# LHC_Clock.net
KiCad netlist of a schematic drawn in Altium Designer
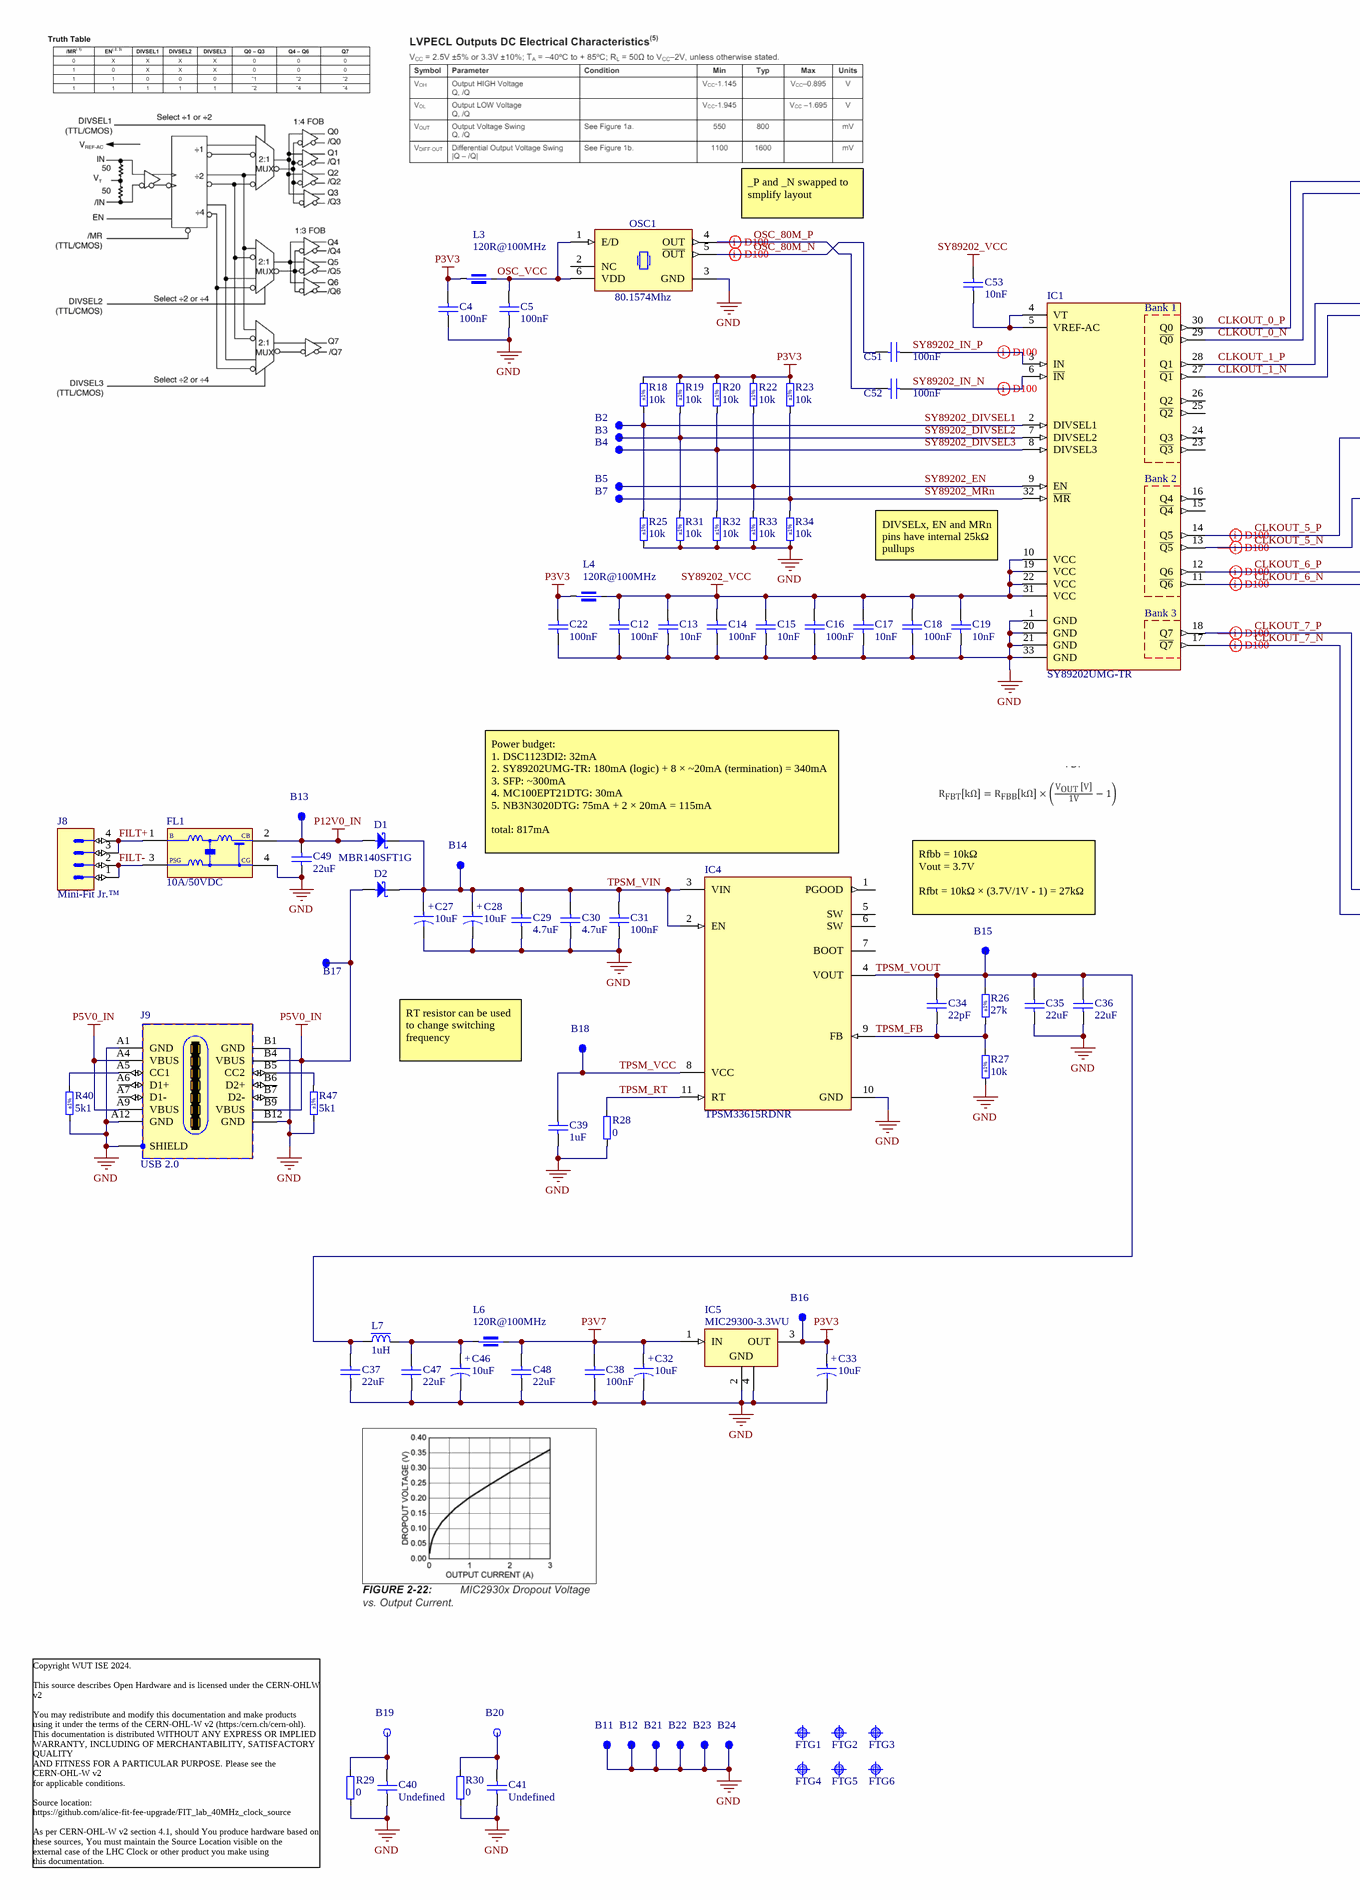
[diagram p0: LHC_Clock.SchDoc, left]
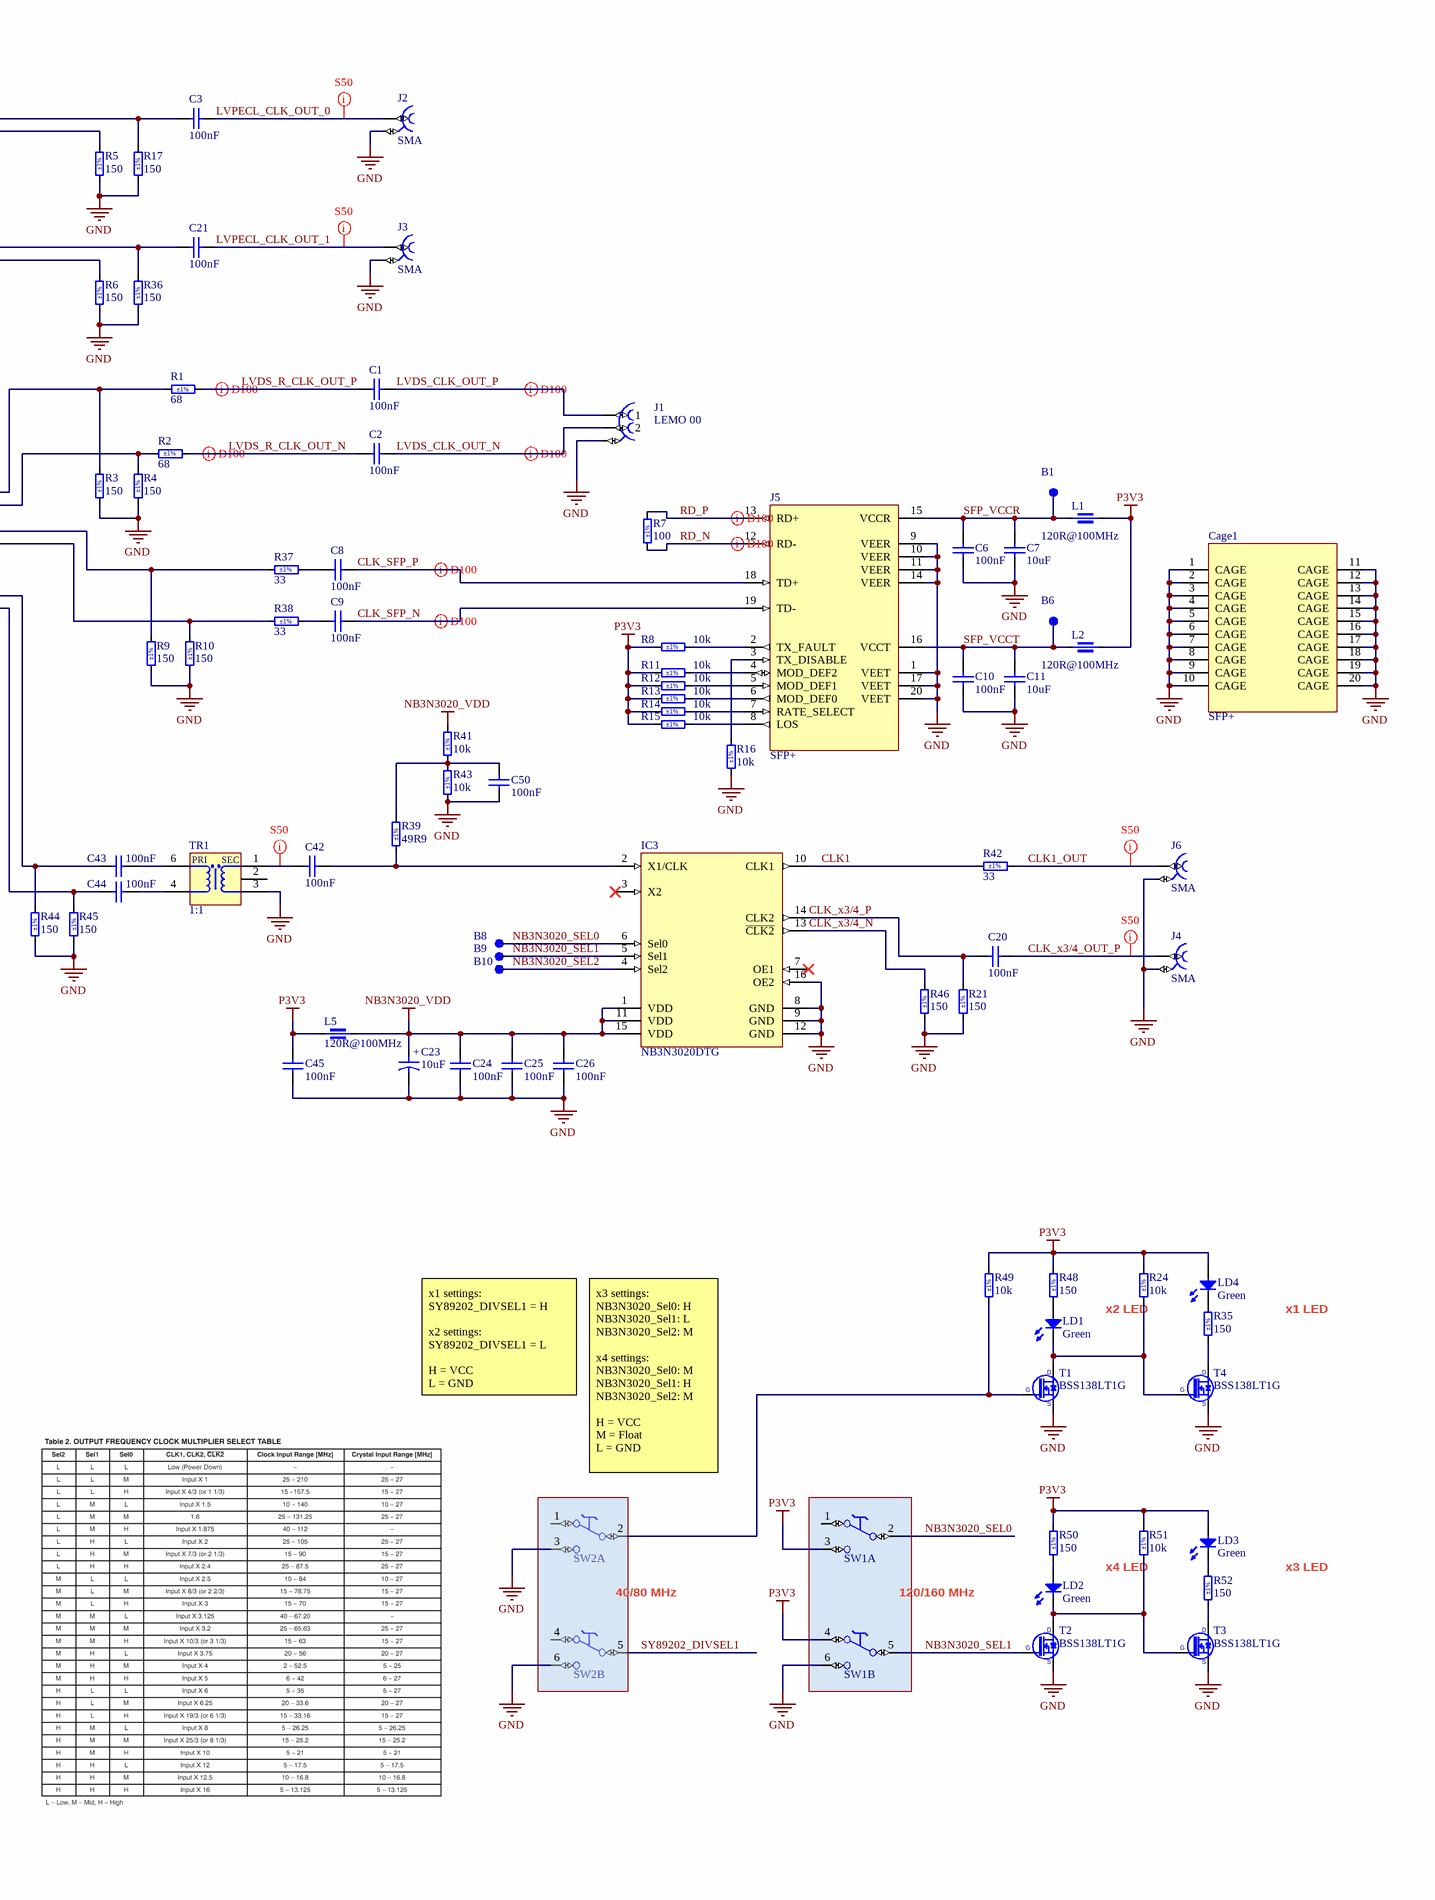
[diagram p1: LHC_Clock.SchDoc, right]

(export (version "E")
  (design (tool "Eeschema 10.0.6"))
  (components
    (comp (ref "B1")
      (value "SMD Pad")
      (footprint "C100")
      (description "Pad")
      (fields (field (name "PART NUMBER") "SMD_PAD_D1MM") (field (name "AUTHOR") "CERN DEM JLC"))
      (libsource (lib "Eletro-mechanical") (part "Single SMD Pad (Round)"))
    )
    (comp (ref "B2")
      (value "SMD Pad")
      (footprint "C100")
      (description "Pad")
      (fields (field (name "PART NUMBER") "SMD_PAD_D1MM") (field (name "AUTHOR") "CERN DEM JLC"))
      (libsource (lib "Eletro-mechanical") (part "Single SMD Pad (Round)"))
    )
    (comp (ref "B3")
      (value "SMD Pad")
      (footprint "C100")
      (description "Pad")
      (fields (field (name "PART NUMBER") "SMD_PAD_D1MM") (field (name "AUTHOR") "CERN DEM JLC"))
      (libsource (lib "Eletro-mechanical") (part "Single SMD Pad (Round)"))
    )
    (comp (ref "B4")
      (value "SMD Pad")
      (footprint "C100")
      (description "Pad")
      (fields (field (name "PART NUMBER") "SMD_PAD_D1MM") (field (name "AUTHOR") "CERN DEM JLC"))
      (libsource (lib "Eletro-mechanical") (part "Single SMD Pad (Round)"))
    )
    (comp (ref "B5")
      (value "SMD Pad")
      (footprint "C100")
      (description "Pad")
      (fields (field (name "PART NUMBER") "SMD_PAD_D1MM") (field (name "AUTHOR") "CERN DEM JLC"))
      (libsource (lib "Eletro-mechanical") (part "Single SMD Pad (Round)"))
    )
    (comp (ref "B6")
      (value "SMD Pad")
      (footprint "C100")
      (description "Pad")
      (fields (field (name "PART NUMBER") "SMD_PAD_D1MM") (field (name "AUTHOR") "CERN DEM JLC"))
      (libsource (lib "Eletro-mechanical") (part "Single SMD Pad (Round)"))
    )
    (comp (ref "B7")
      (value "SMD Pad")
      (footprint "C100")
      (description "Pad")
      (fields (field (name "PART NUMBER") "SMD_PAD_D1MM") (field (name "AUTHOR") "CERN DEM JLC"))
      (libsource (lib "Eletro-mechanical") (part "Single SMD Pad (Round)"))
    )
    (comp (ref "B8")
      (value "SMD Pad")
      (footprint "C100")
      (description "Pad")
      (fields (field (name "PART NUMBER") "SMD_PAD_D1MM") (field (name "AUTHOR") "CERN DEM JLC"))
      (libsource (lib "Eletro-mechanical") (part "Single SMD Pad (Round)"))
    )
    (comp (ref "B9")
      (value "SMD Pad")
      (footprint "C100")
      (description "Pad")
      (fields (field (name "PART NUMBER") "SMD_PAD_D1MM") (field (name "AUTHOR") "CERN DEM JLC"))
      (libsource (lib "Eletro-mechanical") (part "Single SMD Pad (Round)"))
    )
    (comp (ref "B10")
      (value "SMD Pad")
      (footprint "C100")
      (description "Pad")
      (fields (field (name "PART NUMBER") "SMD_PAD_D1MM") (field (name "AUTHOR") "CERN DEM JLC"))
      (libsource (lib "Eletro-mechanical") (part "Single SMD Pad (Round)"))
    )
    (comp (ref "B11")
      (value "SMD Pad")
      (footprint "C100")
      (description "Pad")
      (fields (field (name "PART NUMBER") "SMD_PAD_D1MM") (field (name "AUTHOR") "CERN DEM JLC"))
      (libsource (lib "Eletro-mechanical") (part "Single SMD Pad (Round)"))
    )
    (comp (ref "B12")
      (value "SMD Pad")
      (footprint "C100")
      (description "Pad")
      (fields (field (name "PART NUMBER") "SMD_PAD_D1MM") (field (name "AUTHOR") "CERN DEM JLC"))
      (libsource (lib "Eletro-mechanical") (part "Single SMD Pad (Round)"))
    )
    (comp (ref "B13")
      (value "SMD Pad")
      (footprint "C100")
      (description "Pad")
      (fields (field (name "PART NUMBER") "SMD_PAD_D1MM") (field (name "AUTHOR") "CERN DEM JLC"))
      (libsource (lib "Eletro-mechanical") (part "Single SMD Pad (Round)"))
    )
    (comp (ref "B14")
      (value "SMD Pad")
      (footprint "C100")
      (description "Pad")
      (fields (field (name "PART NUMBER") "SMD_PAD_D1MM") (field (name "AUTHOR") "CERN DEM JLC"))
      (libsource (lib "Eletro-mechanical") (part "Single SMD Pad (Round)"))
    )
    (comp (ref "B15")
      (value "SMD Pad")
      (footprint "C100")
      (description "Pad")
      (fields (field (name "PART NUMBER") "SMD_PAD_D1MM") (field (name "AUTHOR") "CERN DEM JLC"))
      (libsource (lib "Eletro-mechanical") (part "Single SMD Pad (Round)"))
    )
    (comp (ref "B16")
      (value "SMD Pad")
      (footprint "C100")
      (description "Pad")
      (fields (field (name "PART NUMBER") "SMD_PAD_D1MM") (field (name "AUTHOR") "CERN DEM JLC"))
      (libsource (lib "Eletro-mechanical") (part "Single SMD Pad (Round)"))
    )
    (comp (ref "B17")
      (value "SMD Pad")
      (footprint "C100")
      (description "Pad")
      (fields (field (name "PART NUMBER") "SMD_PAD_D1MM") (field (name "AUTHOR") "CERN DEM JLC"))
      (libsource (lib "Eletro-mechanical") (part "Single SMD Pad (Round)"))
    )
    (comp (ref "B18")
      (value "SMD Pad")
      (footprint "C100")
      (description "Pad")
      (fields (field (name "PART NUMBER") "SMD_PAD_D1MM") (field (name "AUTHOR") "CERN DEM JLC"))
      (libsource (lib "Eletro-mechanical") (part "Single SMD Pad (Round)"))
    )
    (comp (ref "B19")
      (value "Plated Hole")
      (footprint "MTG270_500")
      (description "Single Terminal Socket")
      (fields (field (name "PART NUMBER") "PLATED_HOLE2.7_PAD5.0") (field (name "AUTHOR") "CERN DEM JMW"))
      (libsource (lib "Eletro-mechanical") (part "Single Terminal Socket"))
    )
    (comp (ref "B20")
      (value "Plated Hole")
      (footprint "MTG270_500")
      (description "Single Terminal Socket")
      (fields (field (name "PART NUMBER") "PLATED_HOLE2.7_PAD5.0") (field (name "AUTHOR") "CERN DEM JMW"))
      (libsource (lib "Eletro-mechanical") (part "Single Terminal Socket"))
    )
    (comp (ref "B21")
      (value "SMD Pad")
      (footprint "C100")
      (description "Pad")
      (fields (field (name "PART NUMBER") "SMD_PAD_D1MM") (field (name "AUTHOR") "CERN DEM JLC"))
      (libsource (lib "Eletro-mechanical") (part "Single SMD Pad (Round)"))
    )
    (comp (ref "B22")
      (value "SMD Pad")
      (footprint "C100")
      (description "Pad")
      (fields (field (name "PART NUMBER") "SMD_PAD_D1MM") (field (name "AUTHOR") "CERN DEM JLC"))
      (libsource (lib "Eletro-mechanical") (part "Single SMD Pad (Round)"))
    )
    (comp (ref "B23")
      (value "SMD Pad")
      (footprint "C100")
      (description "Pad")
      (fields (field (name "PART NUMBER") "SMD_PAD_D1MM") (field (name "AUTHOR") "CERN DEM JLC"))
      (libsource (lib "Eletro-mechanical") (part "Single SMD Pad (Round)"))
    )
    (comp (ref "B24")
      (value "SMD Pad")
      (footprint "C100")
      (description "Pad")
      (fields (field (name "PART NUMBER") "SMD_PAD_D1MM") (field (name "AUTHOR") "CERN DEM JLC"))
      (libsource (lib "Eletro-mechanical") (part "Single SMD Pad (Round)"))
    )
    (comp (ref "C1")
      (value "100nF")
      (footprint "CAPC1005X55N")
      (description "Non-polarised capacitor")
      (fields
        (field (name "PART NUMBER") "CC0402_100NF_50V_10%_X7R")
        (field (name "VOLTAGE") "50V")
        (field (name "AUTHOR") "CERN DEM MR")
      )
      (libsource (lib "Capacitors") (part "Capacitor - non polarized"))
    )
    (comp (ref "C2")
      (value "100nF")
      (footprint "CAPC1005X55N")
      (description "Non-polarised capacitor")
      (fields
        (field (name "PART NUMBER") "CC0402_100NF_50V_10%_X7R")
        (field (name "VOLTAGE") "50V")
        (field (name "AUTHOR") "CERN DEM MR")
      )
      (libsource (lib "Capacitors") (part "Capacitor - non polarized"))
    )
    (comp (ref "C3")
      (value "100nF")
      (footprint "CAPC1005X55N")
      (description "Non-polarised capacitor")
      (fields
        (field (name "PART NUMBER") "CC0402_100NF_50V_10%_X7R")
        (field (name "VOLTAGE") "50V")
        (field (name "AUTHOR") "CERN DEM MR")
      )
      (libsource (lib "Capacitors") (part "Capacitor - non polarized"))
    )
    (comp (ref "C4")
      (value "100nF")
      (footprint "CAPC1005X55N")
      (description "Non-polarised capacitor")
      (fields
        (field (name "PART NUMBER") "CC0402_100NF_50V_10%_X7R")
        (field (name "VOLTAGE") "50V")
        (field (name "AUTHOR") "CERN DEM MR")
      )
      (libsource (lib "Capacitors") (part "Capacitor - non polarized"))
    )
    (comp (ref "C5")
      (value "100nF")
      (footprint "CAPC1005X55N")
      (description "Non-polarised capacitor")
      (fields
        (field (name "PART NUMBER") "CC0402_100NF_50V_10%_X7R")
        (field (name "VOLTAGE") "50V")
        (field (name "AUTHOR") "CERN DEM MR")
      )
      (libsource (lib "Capacitors") (part "Capacitor - non polarized"))
    )
    (comp (ref "C6")
      (value "100nF")
      (footprint "CAPC1005X55N")
      (description "Non-polarised capacitor")
      (fields
        (field (name "PART NUMBER") "CC0402_100NF_50V_10%_X7R")
        (field (name "VOLTAGE") "50V")
        (field (name "AUTHOR") "CERN DEM MR")
      )
      (libsource (lib "Capacitors") (part "Capacitor - non polarized"))
    )
    (comp (ref "C7")
      (value "10uF")
      (footprint "CAPC1608X80N")
      (description "Non-polarised capacitor")
      (fields
        (field (name "PART NUMBER") "CC0603_10UF_16V_20%_X5R")
        (field (name "VOLTAGE") "16V")
        (field (name "AUTHOR") "CERN DEM MR")
      )
      (libsource (lib "Capacitors") (part "Capacitor - non polarized"))
    )
    (comp (ref "C8")
      (value "100nF")
      (footprint "CAPC1005X55N")
      (description "Non-polarised capacitor")
      (fields
        (field (name "PART NUMBER") "CC0402_100NF_50V_10%_X7R")
        (field (name "VOLTAGE") "50V")
        (field (name "AUTHOR") "CERN DEM MR")
      )
      (libsource (lib "Capacitors") (part "Capacitor - non polarized"))
    )
    (comp (ref "C9")
      (value "100nF")
      (footprint "CAPC1005X55N")
      (description "Non-polarised capacitor")
      (fields
        (field (name "PART NUMBER") "CC0402_100NF_50V_10%_X7R")
        (field (name "VOLTAGE") "50V")
        (field (name "AUTHOR") "CERN DEM MR")
      )
      (libsource (lib "Capacitors") (part "Capacitor - non polarized"))
    )
    (comp (ref "C10")
      (value "100nF")
      (footprint "CAPC1005X55N")
      (description "Non-polarised capacitor")
      (fields
        (field (name "PART NUMBER") "CC0402_100NF_50V_10%_X7R")
        (field (name "VOLTAGE") "50V")
        (field (name "AUTHOR") "CERN DEM MR")
      )
      (libsource (lib "Capacitors") (part "Capacitor - non polarized"))
    )
    (comp (ref "C11")
      (value "10uF")
      (footprint "CAPC1608X80N")
      (description "Non-polarised capacitor")
      (fields
        (field (name "PART NUMBER") "CC0603_10UF_16V_20%_X5R")
        (field (name "VOLTAGE") "16V")
        (field (name "AUTHOR") "CERN DEM MR")
      )
      (libsource (lib "Capacitors") (part "Capacitor - non polarized"))
    )
    (comp (ref "C12")
      (value "100nF")
      (footprint "CAPC1005X55N")
      (description "Non-polarised capacitor")
      (fields
        (field (name "PART NUMBER") "CC0402_100NF_50V_10%_X7R")
        (field (name "VOLTAGE") "50V")
        (field (name "AUTHOR") "CERN DEM MR")
      )
      (libsource (lib "Capacitors") (part "Capacitor - non polarized"))
    )
    (comp (ref "C13")
      (value "10nF")
      (footprint "CAPC1005X55N")
      (description "Non-polarised capacitor")
      (fields
        (field (name "PART NUMBER") "CC0402_10NF_50V_10%_X7R")
        (field (name "VOLTAGE") "50V")
        (field (name "AUTHOR") "CERN DEM MR")
      )
      (libsource (lib "Capacitors") (part "Capacitor - non polarized"))
    )
    (comp (ref "C14")
      (value "100nF")
      (footprint "CAPC1005X55N")
      (description "Non-polarised capacitor")
      (fields
        (field (name "PART NUMBER") "CC0402_100NF_50V_10%_X7R")
        (field (name "VOLTAGE") "50V")
        (field (name "AUTHOR") "CERN DEM MR")
      )
      (libsource (lib "Capacitors") (part "Capacitor - non polarized"))
    )
    (comp (ref "C15")
      (value "10nF")
      (footprint "CAPC1005X55N")
      (description "Non-polarised capacitor")
      (fields
        (field (name "PART NUMBER") "CC0402_10NF_50V_10%_X7R")
        (field (name "VOLTAGE") "50V")
        (field (name "AUTHOR") "CERN DEM MR")
      )
      (libsource (lib "Capacitors") (part "Capacitor - non polarized"))
    )
    (comp (ref "C16")
      (value "100nF")
      (footprint "CAPC1005X55N")
      (description "Non-polarised capacitor")
      (fields
        (field (name "PART NUMBER") "CC0402_100NF_50V_10%_X7R")
        (field (name "VOLTAGE") "50V")
        (field (name "AUTHOR") "CERN DEM MR")
      )
      (libsource (lib "Capacitors") (part "Capacitor - non polarized"))
    )
    (comp (ref "C17")
      (value "10nF")
      (footprint "CAPC1005X55N")
      (description "Non-polarised capacitor")
      (fields
        (field (name "PART NUMBER") "CC0402_10NF_50V_10%_X7R")
        (field (name "VOLTAGE") "50V")
        (field (name "AUTHOR") "CERN DEM MR")
      )
      (libsource (lib "Capacitors") (part "Capacitor - non polarized"))
    )
    (comp (ref "C18")
      (value "100nF")
      (footprint "CAPC1005X55N")
      (description "Non-polarised capacitor")
      (fields
        (field (name "PART NUMBER") "CC0402_100NF_50V_10%_X7R")
        (field (name "VOLTAGE") "50V")
        (field (name "AUTHOR") "CERN DEM MR")
      )
      (libsource (lib "Capacitors") (part "Capacitor - non polarized"))
    )
    (comp (ref "C19")
      (value "10nF")
      (footprint "CAPC1005X55N")
      (description "Non-polarised capacitor")
      (fields
        (field (name "PART NUMBER") "CC0402_10NF_50V_10%_X7R")
        (field (name "VOLTAGE") "50V")
        (field (name "AUTHOR") "CERN DEM MR")
      )
      (libsource (lib "Capacitors") (part "Capacitor - non polarized"))
    )
    (comp (ref "C20")
      (value "100nF")
      (footprint "CAPC1005X55N")
      (description "Non-polarised capacitor")
      (fields
        (field (name "PART NUMBER") "CC0402_100NF_50V_10%_X7R")
        (field (name "VOLTAGE") "50V")
        (field (name "AUTHOR") "CERN DEM MR")
      )
      (libsource (lib "Capacitors") (part "Capacitor - non polarized"))
    )
    (comp (ref "C21")
      (value "100nF")
      (footprint "CAPC1005X55N")
      (description "Non-polarised capacitor")
      (fields
        (field (name "PART NUMBER") "CC0402_100NF_50V_10%_X7R")
        (field (name "VOLTAGE") "50V")
        (field (name "AUTHOR") "CERN DEM MR")
      )
      (libsource (lib "Capacitors") (part "Capacitor - non polarized"))
    )
    (comp (ref "C22")
      (value "100nF")
      (footprint "CAPC1005X55N")
      (description "Non-polarised capacitor")
      (fields
        (field (name "PART NUMBER") "CC0402_100NF_50V_10%_X7R")
        (field (name "VOLTAGE") "50V")
        (field (name "AUTHOR") "CERN DEM MR")
      )
      (libsource (lib "Capacitors") (part "Capacitor - non polarized"))
    )
    (comp (ref "C23")
      (value "10uF")
      (footprint "CAPMP3216X180N")
      (description "Polarised capacitor")
      (fields
        (field (name "PART NUMBER") "CTE3216-18_10UF_16V_20%_AVX_TCJ")
        (field (name "VOLTAGE") "16V")
        (field (name "AUTHOR") "CERN DEM JLC")
      )
      (libsource (lib "Capacitors") (part "Capacitor - polarized"))
    )
    (comp (ref "C24")
      (value "100nF")
      (footprint "CAPC1005X55N")
      (description "Non-polarised capacitor")
      (fields
        (field (name "PART NUMBER") "CC0402_100NF_50V_10%_X7R")
        (field (name "VOLTAGE") "50V")
        (field (name "AUTHOR") "CERN DEM MR")
      )
      (libsource (lib "Capacitors") (part "Capacitor - non polarized"))
    )
    (comp (ref "C25")
      (value "100nF")
      (footprint "CAPC1005X55N")
      (description "Non-polarised capacitor")
      (fields
        (field (name "PART NUMBER") "CC0402_100NF_50V_10%_X7R")
        (field (name "VOLTAGE") "50V")
        (field (name "AUTHOR") "CERN DEM MR")
      )
      (libsource (lib "Capacitors") (part "Capacitor - non polarized"))
    )
    (comp (ref "C26")
      (value "100nF")
      (footprint "CAPC1005X55N")
      (description "Non-polarised capacitor")
      (fields
        (field (name "PART NUMBER") "CC0402_100NF_50V_10%_X7R")
        (field (name "VOLTAGE") "50V")
        (field (name "AUTHOR") "CERN DEM MR")
      )
      (libsource (lib "Capacitors") (part "Capacitor - non polarized"))
    )
    (comp (ref "C27")
      (value "10uF")
      (footprint "CAPMP3216X180N")
      (description "Polarised capacitor")
      (fields
        (field (name "PART NUMBER") "CTE3216-18_10UF_16V_20%_AVX_TCJ")
        (field (name "VOLTAGE") "16V")
        (field (name "AUTHOR") "CERN DEM JLC")
      )
      (libsource (lib "Capacitors") (part "Capacitor - polarized"))
    )
    (comp (ref "C28")
      (value "10uF")
      (footprint "CAPMP3216X180N")
      (description "Polarised capacitor")
      (fields
        (field (name "PART NUMBER") "CTE3216-18_10UF_16V_20%_AVX_TCJ")
        (field (name "VOLTAGE") "16V")
        (field (name "AUTHOR") "CERN DEM JLC")
      )
      (libsource (lib "Capacitors") (part "Capacitor - polarized"))
    )
    (comp (ref "C29")
      (value "4.7uF")
      (footprint "CAPC1608X90N")
      (description "Non-polarised capacitor")
      (fields
        (field (name "PART NUMBER") "CC0603_4.7UF_25V_10%_X5R")
        (field (name "VOLTAGE") "25V")
        (field (name "AUTHOR") "CERN DEM JLC")
      )
      (libsource (lib "Capacitors") (part "Capacitor - non polarized"))
    )
    (comp (ref "C30")
      (value "4.7uF")
      (footprint "CAPC1608X90N")
      (description "Non-polarised capacitor")
      (fields
        (field (name "PART NUMBER") "CC0603_4.7UF_25V_10%_X5R")
        (field (name "VOLTAGE") "25V")
        (field (name "AUTHOR") "CERN DEM JLC")
      )
      (libsource (lib "Capacitors") (part "Capacitor - non polarized"))
    )
    (comp (ref "C31")
      (value "100nF")
      (footprint "CAPC1005X55N")
      (description "Non-polarised capacitor")
      (fields
        (field (name "PART NUMBER") "CC0402_100NF_50V_10%_X7R")
        (field (name "VOLTAGE") "50V")
        (field (name "AUTHOR") "CERN DEM MR")
      )
      (libsource (lib "Capacitors") (part "Capacitor - non polarized"))
    )
    (comp (ref "C32")
      (value "10uF")
      (footprint "CAPMP3216X180N")
      (description "Polarised capacitor")
      (fields
        (field (name "PART NUMBER") "CTE3216-18_10UF_16V_20%_AVX_TCJ")
        (field (name "VOLTAGE") "16V")
        (field (name "AUTHOR") "CERN DEM JLC")
      )
      (libsource (lib "Capacitors") (part "Capacitor - polarized"))
    )
    (comp (ref "C33")
      (value "10uF")
      (footprint "CAPMP3216X180N")
      (description "Polarised capacitor")
      (fields
        (field (name "PART NUMBER") "CTE3216-18_10UF_16V_20%_AVX_TCJ")
        (field (name "VOLTAGE") "16V")
        (field (name "AUTHOR") "CERN DEM JLC")
      )
      (libsource (lib "Capacitors") (part "Capacitor - polarized"))
    )
    (comp (ref "C34")
      (value "22pF")
      (footprint "CAPC1005X55N")
      (description "Non-polarised capacitor")
      (fields
        (field (name "PART NUMBER") "CC0402_22PF_50V_5%_C0G")
        (field (name "VOLTAGE") "50V")
        (field (name "AUTHOR") "CERN DEM JLC")
      )
      (libsource (lib "Capacitors") (part "Capacitor - non polarized"))
    )
    (comp (ref "C35")
      (value "22uF")
      (footprint "CAPC2012X135N")
      (description "Non-polarised capacitor")
      (fields
        (field (name "PART NUMBER") "CC0805_22UF_16V_10%_X5R")
        (field (name "VOLTAGE") "16V")
        (field (name "AUTHOR") "CERN DEM JLC")
      )
      (libsource (lib "Capacitors") (part "Capacitor - non polarized"))
    )
    (comp (ref "C36")
      (value "22uF")
      (footprint "CAPC2012X135N")
      (description "Non-polarised capacitor")
      (fields
        (field (name "PART NUMBER") "CC0805_22UF_16V_10%_X5R")
        (field (name "VOLTAGE") "16V")
        (field (name "AUTHOR") "CERN DEM JLC")
      )
      (libsource (lib "Capacitors") (part "Capacitor - non polarized"))
    )
    (comp (ref "C37")
      (value "22uF")
      (footprint "CAPC2012X135N")
      (description "Non-polarised capacitor")
      (fields
        (field (name "PART NUMBER") "CC0805_22UF_16V_10%_X5R")
        (field (name "VOLTAGE") "16V")
        (field (name "AUTHOR") "CERN DEM JLC")
      )
      (libsource (lib "Capacitors") (part "Capacitor - non polarized"))
    )
    (comp (ref "C38")
      (value "100nF")
      (footprint "CAPC1005X55N")
      (description "Non-polarised capacitor")
      (fields
        (field (name "PART NUMBER") "CC0402_100NF_50V_10%_X7R")
        (field (name "VOLTAGE") "50V")
        (field (name "AUTHOR") "CERN DEM MR")
      )
      (libsource (lib "Capacitors") (part "Capacitor - non polarized"))
    )
    (comp (ref "C39")
      (value "1uF")
      (footprint "CAPC1608X87N")
      (description "Non-polarised capacitor")
      (fields
        (field (name "PART NUMBER") "CC0603_1UF_16V_10%_X7R")
        (field (name "VOLTAGE") "16V")
        (field (name "AUTHOR") "CERN DEM JLC")
      )
      (libsource (lib "Capacitors") (part "Capacitor - non polarized"))
    )
    (comp (ref "C40")
      (value "Undefined")
      (footprint "CAPC2012X135N")
      (description "Non-polarised capacitor")
      (fields (field (name "PART NUMBER") "CC0805_NO-VALUE") (field (name "AUTHOR") "CERN DEM JLC"))
      (libsource (lib "Capacitors") (part "Capacitor - non polarized"))
    )
    (comp (ref "C41")
      (value "Undefined")
      (footprint "CAPC2012X135N")
      (description "Non-polarised capacitor")
      (fields (field (name "PART NUMBER") "CC0805_NO-VALUE") (field (name "AUTHOR") "CERN DEM JLC"))
      (libsource (lib "Capacitors") (part "Capacitor - non polarized"))
    )
    (comp (ref "C42")
      (value "100nF")
      (footprint "CAPC1005X55N")
      (description "Non-polarised capacitor")
      (fields
        (field (name "PART NUMBER") "CC0402_100NF_50V_10%_X7R")
        (field (name "VOLTAGE") "50V")
        (field (name "AUTHOR") "CERN DEM MR")
      )
      (libsource (lib "Capacitors") (part "Capacitor - non polarized"))
    )
    (comp (ref "C43")
      (value "100nF")
      (footprint "CAPC1005X55N")
      (description "Non-polarised capacitor")
      (fields
        (field (name "PART NUMBER") "CC0402_100NF_50V_10%_X7R")
        (field (name "VOLTAGE") "50V")
        (field (name "AUTHOR") "CERN DEM MR")
      )
      (libsource (lib "Capacitors") (part "Capacitor - non polarized"))
    )
    (comp (ref "C44")
      (value "100nF")
      (footprint "CAPC1005X55N")
      (description "Non-polarised capacitor")
      (fields
        (field (name "PART NUMBER") "CC0402_100NF_50V_10%_X7R")
        (field (name "VOLTAGE") "50V")
        (field (name "AUTHOR") "CERN DEM MR")
      )
      (libsource (lib "Capacitors") (part "Capacitor - non polarized"))
    )
    (comp (ref "C45")
      (value "100nF")
      (footprint "CAPC1005X55N")
      (description "Non-polarised capacitor")
      (fields
        (field (name "PART NUMBER") "CC0402_100NF_50V_10%_X7R")
        (field (name "VOLTAGE") "50V")
        (field (name "AUTHOR") "CERN DEM MR")
      )
      (libsource (lib "Capacitors") (part "Capacitor - non polarized"))
    )
    (comp (ref "C46")
      (value "10uF")
      (footprint "CAPMP3216X180N")
      (description "Polarised capacitor")
      (fields
        (field (name "PART NUMBER") "CTE3216-18_10UF_16V_20%_AVX_TCJ")
        (field (name "VOLTAGE") "16V")
        (field (name "AUTHOR") "CERN DEM JLC")
      )
      (libsource (lib "Capacitors") (part "Capacitor - polarized"))
    )
    (comp (ref "C47")
      (value "22uF")
      (footprint "CAPC2012X135N")
      (description "Non-polarised capacitor")
      (fields
        (field (name "PART NUMBER") "CC0805_22UF_16V_10%_X5R")
        (field (name "VOLTAGE") "16V")
        (field (name "AUTHOR") "CERN DEM JLC")
      )
      (libsource (lib "Capacitors") (part "Capacitor - non polarized"))
    )
    (comp (ref "C48")
      (value "22uF")
      (footprint "CAPC2012X135N")
      (description "Non-polarised capacitor")
      (fields
        (field (name "PART NUMBER") "CC0805_22UF_16V_10%_X5R")
        (field (name "VOLTAGE") "16V")
        (field (name "AUTHOR") "CERN DEM JLC")
      )
      (libsource (lib "Capacitors") (part "Capacitor - non polarized"))
    )
    (comp (ref "C49")
      (value "22uF")
      (footprint "CAPC2012X135N")
      (description "Non-polarised capacitor")
      (fields
        (field (name "PART NUMBER") "CC0805_22UF_16V_10%_X5R")
        (field (name "VOLTAGE") "16V")
        (field (name "AUTHOR") "CERN DEM JLC")
      )
      (libsource (lib "Capacitors") (part "Capacitor - non polarized"))
    )
    (comp (ref "C50")
      (value "100nF")
      (footprint "CAPC1005X55N")
      (description "Non-polarised capacitor")
      (fields
        (field (name "PART NUMBER") "CC0402_100NF_50V_10%_X7R")
        (field (name "VOLTAGE") "50V")
        (field (name "AUTHOR") "CERN DEM MR")
      )
      (libsource (lib "Capacitors") (part "Capacitor - non polarized"))
    )
    (comp (ref "C51")
      (value "100nF")
      (footprint "CAPC1005X55N")
      (description "Non-polarised capacitor")
      (fields
        (field (name "PART NUMBER") "CC0402_100NF_50V_10%_X7R")
        (field (name "VOLTAGE") "50V")
        (field (name "AUTHOR") "CERN DEM MR")
      )
      (libsource (lib "Capacitors") (part "Capacitor - non polarized"))
    )
    (comp (ref "C52")
      (value "100nF")
      (footprint "CAPC1005X55N")
      (description "Non-polarised capacitor")
      (fields
        (field (name "PART NUMBER") "CC0402_100NF_50V_10%_X7R")
        (field (name "VOLTAGE") "50V")
        (field (name "AUTHOR") "CERN DEM MR")
      )
      (libsource (lib "Capacitors") (part "Capacitor - non polarized"))
    )
    (comp (ref "C53")
      (value "10nF")
      (footprint "CAPC1005X55N")
      (description "Non-polarised capacitor")
      (fields
        (field (name "PART NUMBER") "CC0402_10NF_50V_10%_X7R")
        (field (name "VOLTAGE") "50V")
        (field (name "AUTHOR") "CERN DEM MR")
      )
      (libsource (lib "Capacitors") (part "Capacitor - non polarized"))
    )
    (comp (ref "Cage1")
      (value "SFP+")
      (footprint "MOLEX_74737-0009")
      (description "SFP+ 1x1 Cage (20Pins)")
      (fields
        (field (name "PART NUMBER") "MOLEX_74737-0009")
        (field (name "MANUFACTURER") "MOLEX")
        (field (name "AUTHOR") "CERN DEM MR")
      )
      (libsource (lib "Connectors") (part "SFP+ 1x1 Cage (20Pins)"))
    )
    (comp (ref "D1")
      (value "MBR140SFT1G")
      (footprint "SOD-123FL")
      (description "Schottky Diode")
      (fields
        (field (name "VOLTAGE") "40V")
        (field (name "POWER") "1A")
        (field (name "AUTHOR") "CERN DEM JLC")
      )
      (libsource (lib "ICs And Semiconductors") (part "Diode Schottky"))
    )
    (comp (ref "D2")
      (value "MBR140SFT1G")
      (footprint "SOD-123FL")
      (description "Schottky Diode")
      (fields
        (field (name "VOLTAGE") "40V")
        (field (name "POWER") "1A")
        (field (name "AUTHOR") "CERN DEM JLC")
      )
      (libsource (lib "ICs And Semiconductors") (part "Diode Schottky"))
    )
    (comp (ref "FL1")
      (value "10A/50VDC")
      (footprint "FIL_MURATA_BNX02")
      (description "Block Type EMIFIL (LC Combined)")
      (fields
        (field (name "PART NUMBER") "FIL_MURATA_BNX022-01L")
        (field (name "MANUFACTURER") "MURATA")
        (field (name "AUTHOR") "CERN DEM JLC")
      )
      (libsource (lib "Inductors & Transformers") (part "FIL_MURATA_BNX02"))
    )
    (comp (ref "FTG1")
      (value "Use only in PCB")
      (footprint "FIDUCIAL_TOP_S100-200")
      (description "Fiducial Target")
      (fields (field (name "PART NUMBER") "FIDUCIAL_TARGET_S100-200") (field (name "AUTHOR") "CERN DEM JLC"))
      (libsource (lib "Eletro-mechanical") (part "Fiducial Target"))
    )
    (comp (ref "FTG2")
      (value "Use only in PCB")
      (footprint "FIDUCIAL_TOP_S100-200")
      (description "Fiducial Target")
      (fields (field (name "PART NUMBER") "FIDUCIAL_TARGET_S100-200") (field (name "AUTHOR") "CERN DEM JLC"))
      (libsource (lib "Eletro-mechanical") (part "Fiducial Target"))
    )
    (comp (ref "FTG3")
      (value "Use only in PCB")
      (footprint "FIDUCIAL_TOP_S100-200")
      (description "Fiducial Target")
      (fields (field (name "PART NUMBER") "FIDUCIAL_TARGET_S100-200") (field (name "AUTHOR") "CERN DEM JLC"))
      (libsource (lib "Eletro-mechanical") (part "Fiducial Target"))
    )
    (comp (ref "FTG4")
      (value "Use only in PCB")
      (footprint "FIDUCIAL_TOP_S100-200")
      (description "Fiducial Target")
      (fields (field (name "PART NUMBER") "FIDUCIAL_TARGET_S100-200") (field (name "AUTHOR") "CERN DEM JLC"))
      (libsource (lib "Eletro-mechanical") (part "Fiducial Target"))
    )
    (comp (ref "FTG5")
      (value "Use only in PCB")
      (footprint "FIDUCIAL_TOP_S100-200")
      (description "Fiducial Target")
      (fields (field (name "PART NUMBER") "FIDUCIAL_TARGET_S100-200") (field (name "AUTHOR") "CERN DEM JLC"))
      (libsource (lib "Eletro-mechanical") (part "Fiducial Target"))
    )
    (comp (ref "FTG6")
      (value "Use only in PCB")
      (footprint "FIDUCIAL_TOP_S100-200")
      (description "Fiducial Target")
      (fields (field (name "PART NUMBER") "FIDUCIAL_TARGET_S100-200") (field (name "AUTHOR") "CERN DEM JLC"))
      (libsource (lib "Eletro-mechanical") (part "Fiducial Target"))
    )
    (comp (ref "IC1")
      (value "SY89202UMG-TR")
      (footprint "QFN50P500X500X90_HS-33N")
      (description "1: 8 LVPECL fanout w/ Divide by 1, 2, 4 Dividers 32 VQFN 5x5x0.9mm T/R RoHS Compliant: Yes")
      (fields (field (name "MANUFACTURER") "Microchip"))
      (libsource (lib "mb") (part "SY89202UMG-TR"))
    )
    (comp (ref "IC3")
      (value "NB3N3020DTG")
      (footprint "TSOP65P640X120-16N")
      (description "Clock Generator 2MHz to 210MHz Input 210MHz Output 16-Pin TSSOP Tube")
      (fields (field (name "MANUFACTURER") "ON Semiconductor"))
      (libsource (lib "mb") (part "NB3N3020DTG"))
    )
    (comp (ref "IC4")
      (value "TPSM33615RDNR")
      (footprint "RDN0011A-MFG")
      (description "3-V to 36-V input, 1 to 15-V output, 1.5-A synchronous buck power module 11-QFN-FCMOD -40 to 125")
      (fields (field (name "MANUFACTURER") "Texas Instruments"))
      (libsource (lib "mb") (part "TPSM33615RDNR"))
    )
    (comp (ref "IC5")
      (value "MIC29300-3.3WU")
      (footprint "TO254P1524X460-4N-S769X1066")
      (description "3-Terminal Regulator 1=IN 2=GND 3=OUT 4=GND")
      (fields (field (name "MANUFACTURER") "MICREL") (field (name "AUTHOR") "CERN DEM JLC"))
      (libsource (lib "ICs And Semiconductors") (part "REG3+1 1IN-2GND-3OUT+4GND"))
    )
    (comp (ref "J1")
      (value "LEMO 00")
      (footprint "LEMO_EPG.00.302.NLN")
      (fields
        (field (name "PART NUMBER") "LEMO_EPG.00.302.NLN")
        (field (name "MANUFACTURER") "LEMO")
        (field (name "MANUFACTURER PART NUMBER") "EPG.00.302.NLN")
        (field (name "AUTHOR") "CERN DEM JLC")
      )
      (libsource (lib "Connectors") (part "Coax_2Female_1Shield"))
    )
    (comp (ref "J2")
      (value "SMA")
      (footprint "AMPHENOL_132203-12")
      (description "RF Connector SMA Right Angle PCB Jack Through Hole 50 Ohm Bulkhead")
      (fields
        (field (name "MANUFACTURER") "Amphenol Connex")
        (field (name "MANUFACTURER PART NUMBER") "132203-12")
      )
      (libsource (lib "mb") (part "132203-12"))
    )
    (comp (ref "J3")
      (value "SMA")
      (footprint "MOLEX_73251-2120")
      (description "50 Ohm, SMA Edge Mount PCB, With Jam Nut And Lock Washer")
      (fields
        (field (name "PART NUMBER") "MOLEX_73251-2120")
        (field (name "MANUFACTURER") "MOLEX")
        (field (name "AUTHOR") "CERN DEM JLC")
      )
      (libsource (lib "mb") (part "CON_SMA_RA_SMD_73251-2120"))
    )
    (comp (ref "J4")
      (value "SMA")
      (footprint "AMPHENOL_132203-12")
      (description "RF Connector SMA Right Angle PCB Jack Through Hole 50 Ohm Bulkhead")
      (fields
        (field (name "MANUFACTURER") "Amphenol Connex")
        (field (name "MANUFACTURER PART NUMBER") "132203-12")
      )
      (libsource (lib "mb") (part "132203-12"))
    )
    (comp (ref "J5")
      (value "SFP+")
      (footprint "MOLEX_74441-0001")
      (description "20 Position SFP  Connector (Small Form-factor Pluggable)")
      (fields
        (field (name "PART NUMBER") "MOLEX_74441-0001")
        (field (name "MANUFACTURER") "MOLEX")
        (field (name "AUTHOR") "CERN DEM MR")
      )
      (libsource (lib "Connectors") (part "SFPx1"))
    )
    (comp (ref "J6")
      (value "SMA")
      (footprint "MOLEX_73251-2120")
      (description "50 Ohm, SMA Edge Mount PCB, With Jam Nut And Lock Washer")
      (fields
        (field (name "PART NUMBER") "MOLEX_73251-2120")
        (field (name "MANUFACTURER") "MOLEX")
        (field (name "AUTHOR") "CERN DEM JLC")
      )
      (libsource (lib "mb") (part "CON_SMA_RA_SMD_73251-2120"))
    )
    (comp (ref "J8")
      (value "Mini-Fit Jr.™")
      (footprint "MOLEX_39-30-0040")
      (description "Connector 4 Male")
      (fields
        (field (name "PART NUMBER") "MOLEX_39-30-0040")
        (field (name "MANUFACTURER") "MOLEX")
        (field (name "AUTHOR") "CERN DEM JLC")
      )
      (libsource (lib "Connectors") (part "Connector 4 Male"))
    )
    (comp (ref "J9")
      (value "USB 2.0")
      (footprint "MOLEX_216989-0001")
      (description "2x7 Pin + 1 Shield  USB Type C Receptacle")
      (fields
        (field (name "PART NUMBER") "MOLEX_216989-0001")
        (field (name "MANUFACTURER") "MOLEX")
        (field (name "AUTHOR") "CERN DEM HF")
      )
      (libsource (lib "Connectors") (part "Connector USB C 14 Pin + 1 Shield"))
    )
    (comp (ref "L1")
      (value "120R@100MHz")
      (footprint "INDC1608X65N")
      (fields
        (field (name "PART NUMBER") "IND0603_MURATA_BLM18SG121TN1D")
        (field (name "POWER") "3A")
        (field (name "TOLERANCE") "±25%")
        (field (name "AUTHOR") "CERN DEM JLC")
      )
      (libsource (lib "Inductors & Transformers") (part "Ferrite Bead"))
    )
    (comp (ref "L2")
      (value "120R@100MHz")
      (footprint "INDC1608X65N")
      (fields
        (field (name "PART NUMBER") "IND0603_MURATA_BLM18SG121TN1D")
        (field (name "POWER") "3A")
        (field (name "TOLERANCE") "±25%")
        (field (name "AUTHOR") "CERN DEM JLC")
      )
      (libsource (lib "Inductors & Transformers") (part "Ferrite Bead"))
    )
    (comp (ref "L3")
      (value "120R@100MHz")
      (footprint "INDC1608X65N")
      (fields
        (field (name "PART NUMBER") "IND0603_MURATA_BLM18SG121TN1D")
        (field (name "POWER") "3A")
        (field (name "TOLERANCE") "±25%")
        (field (name "AUTHOR") "CERN DEM JLC")
      )
      (libsource (lib "Inductors & Transformers") (part "Ferrite Bead"))
    )
    (comp (ref "L4")
      (value "120R@100MHz")
      (footprint "INDC1608X65N")
      (fields
        (field (name "PART NUMBER") "IND0603_MURATA_BLM18SG121TN1D")
        (field (name "POWER") "3A")
        (field (name "TOLERANCE") "±25%")
        (field (name "AUTHOR") "CERN DEM JLC")
      )
      (libsource (lib "Inductors & Transformers") (part "Ferrite Bead"))
    )
    (comp (ref "L5")
      (value "120R@100MHz")
      (footprint "INDC1608X65N")
      (fields
        (field (name "PART NUMBER") "IND0603_MURATA_BLM18SG121TN1D")
        (field (name "POWER") "3A")
        (field (name "TOLERANCE") "±25%")
        (field (name "AUTHOR") "CERN DEM JLC")
      )
      (libsource (lib "Inductors & Transformers") (part "Ferrite Bead"))
    )
    (comp (ref "L6")
      (value "120R@100MHz")
      (footprint "INDC1608X65N")
      (fields
        (field (name "PART NUMBER") "IND0603_MURATA_BLM18SG121TN1D")
        (field (name "POWER") "3A")
        (field (name "TOLERANCE") "±25%")
        (field (name "AUTHOR") "CERN DEM JLC")
      )
      (libsource (lib "Inductors & Transformers") (part "Ferrite Bead"))
    )
    (comp (ref "L7")
      (value "1uH")
      (footprint "IND_COILCRAFT_PFL3215")
      (description "Inductor With Core")
      (fields
        (field (name "PART NUMBER") "IND_1UH_20%_COILCRAFT_PFL3215")
        (field (name "POWER") "1.9A")
        (field (name "AUTHOR") "CERN DEM MR")
      )
      (libsource (lib "Inductors & Transformers") (part "Inductor With Magnetic core"))
    )
    (comp (ref "LD1")
      (value "Green")
      (footprint "LED_AVAGO_HSME-C120")
      (description "LED Green 1C 2A")
      (fields
        (field (name "PART NUMBER") "LED_AVAGO_HSME-C120")
        (field (name "MANUFACTURER") "AVAGO TECHNOLOGIES")
        (field (name "AUTHOR") "CERN DEM JMW")
      )
      (libsource (lib "ICs And Semiconductors") (part "LED Green 1C 2A"))
    )
    (comp (ref "LD2")
      (value "Green")
      (footprint "LED_AVAGO_HSME-C120")
      (description "LED Green 1C 2A")
      (fields
        (field (name "PART NUMBER") "LED_AVAGO_HSME-C120")
        (field (name "MANUFACTURER") "AVAGO TECHNOLOGIES")
        (field (name "AUTHOR") "CERN DEM JMW")
      )
      (libsource (lib "ICs And Semiconductors") (part "LED Green 1C 2A"))
    )
    (comp (ref "LD3")
      (value "Green")
      (footprint "LED_AVAGO_HSME-C120")
      (description "LED Green 1C 2A")
      (fields
        (field (name "PART NUMBER") "LED_AVAGO_HSME-C120")
        (field (name "MANUFACTURER") "AVAGO TECHNOLOGIES")
        (field (name "AUTHOR") "CERN DEM JMW")
      )
      (libsource (lib "ICs And Semiconductors") (part "LED Green 1C 2A"))
    )
    (comp (ref "LD4")
      (value "Green")
      (footprint "LED_AVAGO_HSME-C120")
      (description "LED Green 1C 2A")
      (fields
        (field (name "PART NUMBER") "LED_AVAGO_HSME-C120")
        (field (name "MANUFACTURER") "AVAGO TECHNOLOGIES")
        (field (name "AUTHOR") "CERN DEM JMW")
      )
      (libsource (lib "ICs And Semiconductors") (part "LED Green 1C 2A"))
    )
    (comp (ref "OSC1")
      (value "80.1574Mhz")
      (footprint "OSC_MICROCHIP_DSC11x3D")
      (description "Low-Jitter Precision LVDS Oscillator (DSC1123 Series)")
      (fields
        (field (name "PART NUMBER") "OSC_80.1574MHZ_MICROCHIP_DSC1123DI2")
        (field (name "MANUFACTURER") "MICROCHIP TECHNOLOGY")
        (field (name "AUTHOR") "CERN DEM BC")
      )
      (libsource (lib "ICs And Semiconductors") (part "Oscillator MICROCHIP_DSC1123"))
    )
    (comp (ref "R1")
      (value "68")
      (footprint "RESC1005X40N")
      (description "Resistor - 1%")
      (fields
        (field (name "TOLERANCE") "±1%")
        (field (name "PART NUMBER") "R0402_68R_1%_0.0625W_100PPM")
        (field (name "POWER") "0.0625W")
        (field (name "AUTHOR") "CERN DEM JLC")
      )
      (libsource (lib "Resistors") (part "Resistor - 1%"))
    )
    (comp (ref "R2")
      (value "68")
      (footprint "RESC1005X40N")
      (description "Resistor - 1%")
      (fields
        (field (name "TOLERANCE") "±1%")
        (field (name "PART NUMBER") "R0402_68R_1%_0.0625W_100PPM")
        (field (name "POWER") "0.0625W")
        (field (name "AUTHOR") "CERN DEM JLC")
      )
      (libsource (lib "Resistors") (part "Resistor - 1%"))
    )
    (comp (ref "R3")
      (value "150")
      (footprint "RESC1005X40N")
      (description "Resistor - 1%")
      (fields
        (field (name "TOLERANCE") "±1%")
        (field (name "PART NUMBER") "R0402_150R_1%_0.0625W_100PPM")
        (field (name "POWER") "0.0625W")
        (field (name "AUTHOR") "CERN DEM JLC")
      )
      (libsource (lib "Resistors") (part "Resistor - 1%"))
    )
    (comp (ref "R4")
      (value "150")
      (footprint "RESC1005X40N")
      (description "Resistor - 1%")
      (fields
        (field (name "TOLERANCE") "±1%")
        (field (name "PART NUMBER") "R0402_150R_1%_0.0625W_100PPM")
        (field (name "POWER") "0.0625W")
        (field (name "AUTHOR") "CERN DEM JLC")
      )
      (libsource (lib "Resistors") (part "Resistor - 1%"))
    )
    (comp (ref "R5")
      (value "150")
      (footprint "RESC1005X40N")
      (description "Resistor - 1%")
      (fields
        (field (name "TOLERANCE") "±1%")
        (field (name "PART NUMBER") "R0402_150R_1%_0.0625W_100PPM")
        (field (name "POWER") "0.0625W")
        (field (name "AUTHOR") "CERN DEM JLC")
      )
      (libsource (lib "Resistors") (part "Resistor - 1%"))
    )
    (comp (ref "R6")
      (value "150")
      (footprint "RESC1005X40N")
      (description "Resistor - 1%")
      (fields
        (field (name "TOLERANCE") "±1%")
        (field (name "PART NUMBER") "R0402_150R_1%_0.0625W_100PPM")
        (field (name "POWER") "0.0625W")
        (field (name "AUTHOR") "CERN DEM JLC")
      )
      (libsource (lib "Resistors") (part "Resistor - 1%"))
    )
    (comp (ref "R7")
      (value "100")
      (footprint "RESC1005X40N")
      (description "Resistor - 1%")
      (fields
        (field (name "TOLERANCE") "±1%")
        (field (name "PART NUMBER") "R0402_100R_1%_0.1W_100PPM")
        (field (name "POWER") "0.1W")
        (field (name "AUTHOR") "CERN DEM JLC")
      )
      (libsource (lib "Resistors") (part "Resistor - 1%"))
    )
    (comp (ref "R8")
      (value "10k")
      (footprint "RESC1005X40N")
      (description "Resistor - 1%")
      (fields
        (field (name "TOLERANCE") "±1%")
        (field (name "PART NUMBER") "R0402_10K_1%_0.0625W_100PPM")
        (field (name "POWER") "0.0625W")
        (field (name "AUTHOR") "CERN DEM JLC")
      )
      (libsource (lib "Resistors") (part "Resistor - 1%"))
    )
    (comp (ref "R9")
      (value "150")
      (footprint "RESC1005X40N")
      (description "Resistor - 1%")
      (fields
        (field (name "TOLERANCE") "±1%")
        (field (name "PART NUMBER") "R0402_150R_1%_0.0625W_100PPM")
        (field (name "POWER") "0.0625W")
        (field (name "AUTHOR") "CERN DEM JLC")
      )
      (libsource (lib "Resistors") (part "Resistor - 1%"))
    )
    (comp (ref "R10")
      (value "150")
      (footprint "RESC1005X40N")
      (description "Resistor - 1%")
      (fields
        (field (name "TOLERANCE") "±1%")
        (field (name "PART NUMBER") "R0402_150R_1%_0.0625W_100PPM")
        (field (name "POWER") "0.0625W")
        (field (name "AUTHOR") "CERN DEM JLC")
      )
      (libsource (lib "Resistors") (part "Resistor - 1%"))
    )
    (comp (ref "R11")
      (value "10k")
      (footprint "RESC1005X40N")
      (description "Resistor - 1%")
      (fields
        (field (name "TOLERANCE") "±1%")
        (field (name "PART NUMBER") "R0402_10K_1%_0.0625W_100PPM")
        (field (name "POWER") "0.0625W")
        (field (name "AUTHOR") "CERN DEM JLC")
      )
      (libsource (lib "Resistors") (part "Resistor - 1%"))
    )
    (comp (ref "R12")
      (value "10k")
      (footprint "RESC1005X40N")
      (description "Resistor - 1%")
      (fields
        (field (name "TOLERANCE") "±1%")
        (field (name "PART NUMBER") "R0402_10K_1%_0.0625W_100PPM")
        (field (name "POWER") "0.0625W")
        (field (name "AUTHOR") "CERN DEM JLC")
      )
      (libsource (lib "Resistors") (part "Resistor - 1%"))
    )
    (comp (ref "R13")
      (value "10k")
      (footprint "RESC1005X40N")
      (description "Resistor - 1%")
      (fields
        (field (name "TOLERANCE") "±1%")
        (field (name "PART NUMBER") "R0402_10K_1%_0.0625W_100PPM")
        (field (name "POWER") "0.0625W")
        (field (name "AUTHOR") "CERN DEM JLC")
      )
      (libsource (lib "Resistors") (part "Resistor - 1%"))
    )
    (comp (ref "R14")
      (value "10k")
      (footprint "RESC1005X40N")
      (description "Resistor - 1%")
      (fields
        (field (name "TOLERANCE") "±1%")
        (field (name "PART NUMBER") "R0402_10K_1%_0.0625W_100PPM")
        (field (name "POWER") "0.0625W")
        (field (name "AUTHOR") "CERN DEM JLC")
      )
      (libsource (lib "Resistors") (part "Resistor - 1%"))
    )
    (comp (ref "R15")
      (value "10k")
      (footprint "RESC1005X40N")
      (description "Resistor - 1%")
      (fields
        (field (name "TOLERANCE") "±1%")
        (field (name "PART NUMBER") "R0402_10K_1%_0.0625W_100PPM")
        (field (name "POWER") "0.0625W")
        (field (name "AUTHOR") "CERN DEM JLC")
      )
      (libsource (lib "Resistors") (part "Resistor - 1%"))
    )
    (comp (ref "R16")
      (value "10k")
      (footprint "RESC1005X40N")
      (description "Resistor - 1%")
      (fields
        (field (name "TOLERANCE") "±1%")
        (field (name "PART NUMBER") "R0402_10K_1%_0.0625W_100PPM")
        (field (name "POWER") "0.0625W")
        (field (name "AUTHOR") "CERN DEM JLC")
      )
      (libsource (lib "Resistors") (part "Resistor - 1%"))
    )
    (comp (ref "R17")
      (value "150")
      (footprint "RESC1005X40N")
      (description "Resistor - 1%")
      (fields
        (field (name "TOLERANCE") "±1%")
        (field (name "PART NUMBER") "R0402_150R_1%_0.0625W_100PPM")
        (field (name "POWER") "0.0625W")
        (field (name "AUTHOR") "CERN DEM JLC")
      )
      (libsource (lib "Resistors") (part "Resistor - 1%"))
    )
    (comp (ref "R18")
      (value "10k")
      (footprint "RESC1005X40N")
      (description "Resistor - 1%")
      (fields
        (field (name "TOLERANCE") "±1%")
        (field (name "PART NUMBER") "R0402_10K_1%_0.0625W_100PPM")
        (field (name "POWER") "0.0625W")
        (field (name "AUTHOR") "CERN DEM JLC")
      )
      (libsource (lib "Resistors") (part "Resistor - 1%"))
    )
    (comp (ref "R19")
      (value "10k")
      (footprint "RESC1005X40N")
      (description "Resistor - 1%")
      (fields
        (field (name "TOLERANCE") "±1%")
        (field (name "PART NUMBER") "R0402_10K_1%_0.0625W_100PPM")
        (field (name "POWER") "0.0625W")
        (field (name "AUTHOR") "CERN DEM JLC")
      )
      (libsource (lib "Resistors") (part "Resistor - 1%"))
    )
    (comp (ref "R20")
      (value "10k")
      (footprint "RESC1005X40N")
      (description "Resistor - 1%")
      (fields
        (field (name "TOLERANCE") "±1%")
        (field (name "PART NUMBER") "R0402_10K_1%_0.0625W_100PPM")
        (field (name "POWER") "0.0625W")
        (field (name "AUTHOR") "CERN DEM JLC")
      )
      (libsource (lib "Resistors") (part "Resistor - 1%"))
    )
    (comp (ref "R21")
      (value "150")
      (footprint "RESC1005X40N")
      (description "Resistor - 1%")
      (fields
        (field (name "TOLERANCE") "±1%")
        (field (name "PART NUMBER") "R0402_150R_1%_0.0625W_100PPM")
        (field (name "POWER") "0.0625W")
        (field (name "AUTHOR") "CERN DEM JLC")
      )
      (libsource (lib "Resistors") (part "Resistor - 1%"))
    )
    (comp (ref "R22")
      (value "10k")
      (footprint "RESC1005X40N")
      (description "Resistor - 1%")
      (fields
        (field (name "TOLERANCE") "±1%")
        (field (name "PART NUMBER") "R0402_10K_1%_0.0625W_100PPM")
        (field (name "POWER") "0.0625W")
        (field (name "AUTHOR") "CERN DEM JLC")
      )
      (libsource (lib "Resistors") (part "Resistor - 1%"))
    )
    (comp (ref "R23")
      (value "10k")
      (footprint "RESC1005X40N")
      (description "Resistor - 1%")
      (fields
        (field (name "TOLERANCE") "±1%")
        (field (name "PART NUMBER") "R0402_10K_1%_0.0625W_100PPM")
        (field (name "POWER") "0.0625W")
        (field (name "AUTHOR") "CERN DEM JLC")
      )
      (libsource (lib "Resistors") (part "Resistor - 1%"))
    )
    (comp (ref "R24")
      (value "10k")
      (footprint "RESC1005X40N")
      (description "Resistor - 1%")
      (fields
        (field (name "TOLERANCE") "±1%")
        (field (name "PART NUMBER") "R0402_10K_1%_0.0625W_100PPM")
        (field (name "POWER") "0.0625W")
        (field (name "AUTHOR") "CERN DEM JLC")
      )
      (libsource (lib "Resistors") (part "Resistor - 1%"))
    )
    (comp (ref "R25")
      (value "10k")
      (footprint "RESC1005X40N")
      (description "Resistor - 1%")
      (fields
        (field (name "TOLERANCE") "±1%")
        (field (name "PART NUMBER") "R0402_10K_1%_0.0625W_100PPM")
        (field (name "POWER") "0.0625W")
        (field (name "AUTHOR") "CERN DEM JLC")
      )
      (libsource (lib "Resistors") (part "Resistor - 1%"))
    )
    (comp (ref "R26")
      (value "27k")
      (footprint "RESC1005X40N")
      (description "Resistor - 1%")
      (fields
        (field (name "TOLERANCE") "±1%")
        (field (name "PART NUMBER") "R0402_27K_1%_0.0625W_100PPM")
        (field (name "POWER") "0.0625W")
        (field (name "AUTHOR") "CERN DEM JLC")
      )
      (libsource (lib "Resistors") (part "Resistor - 1%"))
    )
    (comp (ref "R27")
      (value "10k")
      (footprint "RESC1005X40N")
      (description "Resistor - 1%")
      (fields
        (field (name "TOLERANCE") "±1%")
        (field (name "PART NUMBER") "R0402_10K_1%_0.0625W_100PPM")
        (field (name "POWER") "0.0625W")
        (field (name "AUTHOR") "CERN DEM JLC")
      )
      (libsource (lib "Resistors") (part "Resistor - 1%"))
    )
    (comp (ref "R28")
      (value "0")
      (footprint "RESC1005X40N")
      (description "Resistor")
      (fields
        (field (name "PART NUMBER") "R0402_0R_JUMPER")
        (field (name "MANUFACTURER") "GENERIC")
        (field (name "AUTHOR") "CERN DEM JLC")
      )
      (libsource (lib "Resistors") (part "Resistor"))
    )
    (comp (ref "R29")
      (value "0")
      (footprint "RESC1608X55N")
      (description "Resistor")
      (fields
        (field (name "PART NUMBER") "R0603_0R_JUMPER")
        (field (name "MANUFACTURER") "GENERIC")
        (field (name "AUTHOR") "CERN DEM JLC")
      )
      (libsource (lib "Resistors") (part "Resistor"))
    )
    (comp (ref "R30")
      (value "0")
      (footprint "RESC1608X55N")
      (description "Resistor")
      (fields
        (field (name "PART NUMBER") "R0603_0R_JUMPER")
        (field (name "MANUFACTURER") "GENERIC")
        (field (name "AUTHOR") "CERN DEM JLC")
      )
      (libsource (lib "Resistors") (part "Resistor"))
    )
    (comp (ref "R31")
      (value "10k")
      (footprint "RESC1005X40N")
      (description "Resistor - 1%")
      (fields
        (field (name "TOLERANCE") "±1%")
        (field (name "PART NUMBER") "R0402_10K_1%_0.0625W_100PPM")
        (field (name "POWER") "0.0625W")
        (field (name "AUTHOR") "CERN DEM JLC")
      )
      (libsource (lib "Resistors") (part "Resistor - 1%"))
    )
    (comp (ref "R32")
      (value "10k")
      (footprint "RESC1005X40N")
      (description "Resistor - 1%")
      (fields
        (field (name "TOLERANCE") "±1%")
        (field (name "PART NUMBER") "R0402_10K_1%_0.0625W_100PPM")
        (field (name "POWER") "0.0625W")
        (field (name "AUTHOR") "CERN DEM JLC")
      )
      (libsource (lib "Resistors") (part "Resistor - 1%"))
    )
    (comp (ref "R33")
      (value "10k")
      (footprint "RESC1005X40N")
      (description "Resistor - 1%")
      (fields
        (field (name "TOLERANCE") "±1%")
        (field (name "PART NUMBER") "R0402_10K_1%_0.0625W_100PPM")
        (field (name "POWER") "0.0625W")
        (field (name "AUTHOR") "CERN DEM JLC")
      )
      (libsource (lib "Resistors") (part "Resistor - 1%"))
    )
    (comp (ref "R34")
      (value "10k")
      (footprint "RESC1005X40N")
      (description "Resistor - 1%")
      (fields
        (field (name "TOLERANCE") "±1%")
        (field (name "PART NUMBER") "R0402_10K_1%_0.0625W_100PPM")
        (field (name "POWER") "0.0625W")
        (field (name "AUTHOR") "CERN DEM JLC")
      )
      (libsource (lib "Resistors") (part "Resistor - 1%"))
    )
    (comp (ref "R35")
      (value "150")
      (footprint "RESC1005X40N")
      (description "Resistor - 1%")
      (fields
        (field (name "TOLERANCE") "±1%")
        (field (name "PART NUMBER") "R0402_150R_1%_0.0625W_100PPM")
        (field (name "POWER") "0.0625W")
        (field (name "AUTHOR") "CERN DEM JLC")
      )
      (libsource (lib "Resistors") (part "Resistor - 1%"))
    )
    (comp (ref "R36")
      (value "150")
      (footprint "RESC1005X40N")
      (description "Resistor - 1%")
      (fields
        (field (name "TOLERANCE") "±1%")
        (field (name "PART NUMBER") "R0402_150R_1%_0.0625W_100PPM")
        (field (name "POWER") "0.0625W")
        (field (name "AUTHOR") "CERN DEM JLC")
      )
      (libsource (lib "Resistors") (part "Resistor - 1%"))
    )
    (comp (ref "R37")
      (value "33")
      (footprint "RESC1005X40N")
      (description "Resistor - 1%")
      (fields
        (field (name "TOLERANCE") "±1%")
        (field (name "PART NUMBER") "R0402_33R_1%_0.0625W_100PPM")
        (field (name "POWER") "0.0625W")
        (field (name "AUTHOR") "CERN DEM JLC")
      )
      (libsource (lib "Resistors") (part "Resistor - 1%"))
    )
    (comp (ref "R38")
      (value "33")
      (footprint "RESC1005X40N")
      (description "Resistor - 1%")
      (fields
        (field (name "TOLERANCE") "±1%")
        (field (name "PART NUMBER") "R0402_33R_1%_0.0625W_100PPM")
        (field (name "POWER") "0.0625W")
        (field (name "AUTHOR") "CERN DEM JLC")
      )
      (libsource (lib "Resistors") (part "Resistor - 1%"))
    )
    (comp (ref "R39")
      (value "49R9")
      (footprint "RESC1005X40N")
      (description "Resistor - 1%")
      (fields
        (field (name "TOLERANCE") "±1%")
        (field (name "PART NUMBER") "R0402_49R9_1%_0.0625W_100PPM")
        (field (name "POWER") "0.0625W")
        (field (name "AUTHOR") "CERN DEM JLC")
      )
      (libsource (lib "Resistors") (part "Resistor - 1%"))
    )
    (comp (ref "R40")
      (value "5k1")
      (footprint "RESC1005X40N")
      (description "Resistor - 1%")
      (fields
        (field (name "TOLERANCE") "±1%")
        (field (name "PART NUMBER") "R0402_5K1_1%_0.0625W_100PPM")
        (field (name "POWER") "0.0625W")
        (field (name "AUTHOR") "CERN DEM JLC")
      )
      (libsource (lib "Resistors") (part "Resistor - 1%"))
    )
    (comp (ref "R41")
      (value "10k")
      (footprint "RESC1005X40N")
      (description "Resistor - 1%")
      (fields
        (field (name "TOLERANCE") "±1%")
        (field (name "PART NUMBER") "R0402_10K_1%_0.0625W_100PPM")
        (field (name "POWER") "0.0625W")
        (field (name "AUTHOR") "CERN DEM JLC")
      )
      (libsource (lib "Resistors") (part "Resistor - 1%"))
    )
    (comp (ref "R42")
      (value "33")
      (footprint "RESC1005X40N")
      (description "Resistor - 1%")
      (fields
        (field (name "TOLERANCE") "±1%")
        (field (name "PART NUMBER") "R0402_33R_1%_0.0625W_100PPM")
        (field (name "POWER") "0.0625W")
        (field (name "AUTHOR") "CERN DEM JLC")
      )
      (libsource (lib "Resistors") (part "Resistor - 1%"))
    )
    (comp (ref "R43")
      (value "10k")
      (footprint "RESC1005X40N")
      (description "Resistor - 1%")
      (fields
        (field (name "TOLERANCE") "±1%")
        (field (name "PART NUMBER") "R0402_10K_1%_0.0625W_100PPM")
        (field (name "POWER") "0.0625W")
        (field (name "AUTHOR") "CERN DEM JLC")
      )
      (libsource (lib "Resistors") (part "Resistor - 1%"))
    )
    (comp (ref "R44")
      (value "150")
      (footprint "RESC1005X40N")
      (description "Resistor - 1%")
      (fields
        (field (name "TOLERANCE") "±1%")
        (field (name "PART NUMBER") "R0402_150R_1%_0.0625W_100PPM")
        (field (name "POWER") "0.0625W")
        (field (name "AUTHOR") "CERN DEM JLC")
      )
      (libsource (lib "Resistors") (part "Resistor - 1%"))
    )
    (comp (ref "R45")
      (value "150")
      (footprint "RESC1005X40N")
      (description "Resistor - 1%")
      (fields
        (field (name "TOLERANCE") "±1%")
        (field (name "PART NUMBER") "R0402_150R_1%_0.0625W_100PPM")
        (field (name "POWER") "0.0625W")
        (field (name "AUTHOR") "CERN DEM JLC")
      )
      (libsource (lib "Resistors") (part "Resistor - 1%"))
    )
    (comp (ref "R46")
      (value "150")
      (footprint "RESC1005X40N")
      (description "Resistor - 1%")
      (fields
        (field (name "TOLERANCE") "±1%")
        (field (name "PART NUMBER") "R0402_150R_1%_0.0625W_100PPM")
        (field (name "POWER") "0.0625W")
        (field (name "AUTHOR") "CERN DEM JLC")
      )
      (libsource (lib "Resistors") (part "Resistor - 1%"))
    )
    (comp (ref "R47")
      (value "5k1")
      (footprint "RESC1005X40N")
      (description "Resistor - 1%")
      (fields
        (field (name "TOLERANCE") "±1%")
        (field (name "PART NUMBER") "R0402_5K1_1%_0.0625W_100PPM")
        (field (name "POWER") "0.0625W")
        (field (name "AUTHOR") "CERN DEM JLC")
      )
      (libsource (lib "Resistors") (part "Resistor - 1%"))
    )
    (comp (ref "R48")
      (value "150")
      (footprint "RESC1005X40N")
      (description "Resistor - 1%")
      (fields
        (field (name "TOLERANCE") "±1%")
        (field (name "PART NUMBER") "R0402_150R_1%_0.0625W_100PPM")
        (field (name "POWER") "0.0625W")
        (field (name "AUTHOR") "CERN DEM JLC")
      )
      (libsource (lib "Resistors") (part "Resistor - 1%"))
    )
    (comp (ref "R49")
      (value "10k")
      (footprint "RESC1005X40N")
      (description "Resistor - 1%")
      (fields
        (field (name "TOLERANCE") "±1%")
        (field (name "PART NUMBER") "R0402_10K_1%_0.0625W_100PPM")
        (field (name "POWER") "0.0625W")
        (field (name "AUTHOR") "CERN DEM JLC")
      )
      (libsource (lib "Resistors") (part "Resistor - 1%"))
    )
    (comp (ref "R50")
      (value "150")
      (footprint "RESC1005X40N")
      (description "Resistor - 1%")
      (fields
        (field (name "TOLERANCE") "±1%")
        (field (name "PART NUMBER") "R0402_150R_1%_0.0625W_100PPM")
        (field (name "POWER") "0.0625W")
        (field (name "AUTHOR") "CERN DEM JLC")
      )
      (libsource (lib "Resistors") (part "Resistor - 1%"))
    )
    (comp (ref "R51")
      (value "10k")
      (footprint "RESC1005X40N")
      (description "Resistor - 1%")
      (fields
        (field (name "TOLERANCE") "±1%")
        (field (name "PART NUMBER") "R0402_10K_1%_0.0625W_100PPM")
        (field (name "POWER") "0.0625W")
        (field (name "AUTHOR") "CERN DEM JLC")
      )
      (libsource (lib "Resistors") (part "Resistor - 1%"))
    )
    (comp (ref "R52")
      (value "150")
      (footprint "RESC1005X40N")
      (description "Resistor - 1%")
      (fields
        (field (name "TOLERANCE") "±1%")
        (field (name "PART NUMBER") "R0402_150R_1%_0.0625W_100PPM")
        (field (name "POWER") "0.0625W")
        (field (name "AUTHOR") "CERN DEM JLC")
      )
      (libsource (lib "Resistors") (part "Resistor - 1%"))
    )
    (comp (ref "SW1")
      (value "Switch")
      (footprint "SW_C&K_JS202011CQN")
      (description "DPDTSwitch")
      (fields
        (field (name "PART NUMBER") "SW_C&K_JS202011CQN")
        (field (name "MANUFACTURER") "C&K")
        (field (name "AUTHOR") "CERN DEM MR")
      )
      (libsource (lib "") (part "SW DPDT 1NC-2C-3NO-4NC-5C-6NO_1"))
    )
    (comp (ref "SW2")
      (value "Switch")
      (footprint "SW_C&K_JS202011CQN")
      (description "DPDTSwitch")
      (fields
        (field (name "PART NUMBER") "SW_C&K_JS202011CQN")
        (field (name "MANUFACTURER") "C&K")
        (field (name "AUTHOR") "CERN DEM MR")
      )
      (libsource (lib "") (part "SW DPDT 1NC-2C-3NO-4NC-5C-6NO_1"))
    )
    (comp (ref "T1")
      (value "BSS138LT1G")
      (footprint "SOT95P240X110-3N")
      (description "N-CHANNEL MOSFET WITH DIODE")
      (fields
        (field (name "MANUFACTURER") "ON SEMICONDUCTOR")
        (field (name "MANUFACTURER PART NUMBER") "BSS138L")
        (field (name "AUTHOR") "CERN DEM JLC")
      )
      (libsource (lib "ICs And Semiconductors") (part "N-MOSFET-D 1G 2S 3D"))
    )
    (comp (ref "T2")
      (value "BSS138LT1G")
      (footprint "SOT95P240X110-3N")
      (description "N-CHANNEL MOSFET WITH DIODE")
      (fields
        (field (name "MANUFACTURER") "ON SEMICONDUCTOR")
        (field (name "MANUFACTURER PART NUMBER") "BSS138L")
        (field (name "AUTHOR") "CERN DEM JLC")
      )
      (libsource (lib "ICs And Semiconductors") (part "N-MOSFET-D 1G 2S 3D"))
    )
    (comp (ref "T3")
      (value "BSS138LT1G")
      (footprint "SOT95P240X110-3N")
      (description "N-CHANNEL MOSFET WITH DIODE")
      (fields
        (field (name "MANUFACTURER") "ON SEMICONDUCTOR")
        (field (name "MANUFACTURER PART NUMBER") "BSS138L")
        (field (name "AUTHOR") "CERN DEM JLC")
      )
      (libsource (lib "ICs And Semiconductors") (part "N-MOSFET-D 1G 2S 3D"))
    )
    (comp (ref "T4")
      (value "BSS138LT1G")
      (footprint "SOT95P240X110-3N")
      (description "N-CHANNEL MOSFET WITH DIODE")
      (fields
        (field (name "MANUFACTURER") "ON SEMICONDUCTOR")
        (field (name "MANUFACTURER PART NUMBER") "BSS138L")
        (field (name "AUTHOR") "CERN DEM JLC")
      )
      (libsource (lib "ICs And Semiconductors") (part "N-MOSFET-D 1G 2S 3D"))
    )
    (comp (ref "TR1")
      (value "1:1")
      (footprint "XFMR_MINI-CIRCUITS_AT224-1")
      (description "50 Ohm 1.5 To 500MHz RF Transformers")
      (fields
        (field (name "PART NUMBER") "XFMR_MINI-CIRCUITS_TC1-1+")
        (field (name "MANUFACTURER") "MINI-CIRCUITS")
        (field (name "AUTHOR") "CERN DEM JLC")
      )
      (libsource (lib "Inductors & Transformers") (part "XFMR_MINI-CIRCUITS_TC1-1+"))
    )
  )
  (nets
    (net (code "1") (name "/CLK1") (class "Default")
      (node (ref "IC3") (pin "10") (pinfunction "CLK1_10") (pintype "output"))
      (node (ref "R42") (pin "1") (pinfunction "1_1") (pintype "passive"))
    )
    (net (code "2") (name "/CLK1_OUT") (class "Default")
      (node (ref "J6") (pin "1") (pinfunction "1_1") (pintype "bidirectional"))
      (node (ref "R42") (pin "2") (pinfunction "2_2") (pintype "passive"))
    )
    (net (code "3") (name "/CLKOUT_0_N") (class "Default")
      (node (ref "IC1") (pin "29") (pinfunction "~{Q0}_29") (pintype "output"))
      (node (ref "R5") (pin "2") (pinfunction "2_2") (pintype "passive"))
    )
    (net (code "4") (name "/CLKOUT_0_P") (class "Default")
      (node (ref "C3") (pin "1") (pinfunction "1_1") (pintype "passive"))
      (node (ref "IC1") (pin "30") (pinfunction "Q0_30") (pintype "output"))
      (node (ref "R17") (pin "2") (pinfunction "2_2") (pintype "passive"))
    )
    (net (code "5") (name "/CLKOUT_1_N") (class "Default")
      (node (ref "IC1") (pin "27") (pinfunction "~{Q1}_27") (pintype "output"))
      (node (ref "R6") (pin "2") (pinfunction "2_2") (pintype "passive"))
    )
    (net (code "6") (name "/CLKOUT_1_P") (class "Default")
      (node (ref "C21") (pin "1") (pinfunction "1_1") (pintype "passive"))
      (node (ref "IC1") (pin "28") (pinfunction "Q1_28") (pintype "output"))
      (node (ref "R36") (pin "2") (pinfunction "2_2") (pintype "passive"))
    )
    (net (code "7") (name "/CLKOUT_5_N") (class "Default")
      (node (ref "IC1") (pin "13") (pinfunction "~{Q5}_13") (pintype "output"))
      (node (ref "R2") (pin "1") (pinfunction "1_1") (pintype "passive"))
      (node (ref "R4") (pin "2") (pinfunction "2_2") (pintype "passive"))
    )
    (net (code "8") (name "/CLKOUT_5_P") (class "Default")
      (node (ref "IC1") (pin "14") (pinfunction "Q5_14") (pintype "output"))
      (node (ref "R1") (pin "1") (pinfunction "1_1") (pintype "passive"))
      (node (ref "R3") (pin "2") (pinfunction "2_2") (pintype "passive"))
    )
    (net (code "9") (name "/CLKOUT_6_N") (class "Default")
      (node (ref "IC1") (pin "11") (pinfunction "~{Q6}_11") (pintype "output"))
      (node (ref "R10") (pin "2") (pinfunction "2_2") (pintype "passive"))
      (node (ref "R38") (pin "1") (pinfunction "1_1") (pintype "passive"))
    )
    (net (code "10") (name "/CLKOUT_6_P") (class "Default")
      (node (ref "IC1") (pin "12") (pinfunction "Q6_12") (pintype "output"))
      (node (ref "R37") (pin "1") (pinfunction "1_1") (pintype "passive"))
      (node (ref "R9") (pin "2") (pinfunction "2_2") (pintype "passive"))
    )
    (net (code "11") (name "/CLKOUT_7_N") (class "Default")
      (node (ref "C44") (pin "1") (pinfunction "1_1") (pintype "passive"))
      (node (ref "IC1") (pin "17") (pinfunction "~{Q7}_17") (pintype "output"))
      (node (ref "R45") (pin "2") (pinfunction "2_2") (pintype "passive"))
    )
    (net (code "12") (name "/CLKOUT_7_P") (class "Default")
      (node (ref "C43") (pin "1") (pinfunction "1_1") (pintype "passive"))
      (node (ref "IC1") (pin "18") (pinfunction "Q7_18") (pintype "output"))
      (node (ref "R44") (pin "2") (pinfunction "2_2") (pintype "passive"))
    )
    (net (code "13") (name "/CLK_SFP_N") (class "Default")
      (node (ref "C9") (pin "1") (pinfunction "1_1") (pintype "passive"))
      (node (ref "J5") (pin "19") (pinfunction "TD-_19") (pintype "input"))
    )
    (net (code "14") (name "/CLK_SFP_P") (class "Default")
      (node (ref "C8") (pin "2") (pinfunction "2_2") (pintype "passive"))
      (node (ref "J5") (pin "18") (pinfunction "TD+_18") (pintype "input"))
    )
    (net (code "15") (name "/CLK_x3{slash}4_N") (class "Default")
      (node (ref "IC3") (pin "13") (pinfunction "~{CLK2}_13") (pintype "output"))
      (node (ref "R46") (pin "2") (pinfunction "2_2") (pintype "passive"))
    )
    (net (code "16") (name "/CLK_x3{slash}4_OUT_P") (class "Default")
      (node (ref "C20") (pin "2") (pinfunction "2_2") (pintype "passive"))
      (node (ref "J4") (pin "1") (pinfunction "1_1") (pintype "bidirectional"))
    )
    (net (code "17") (name "/CLK_x3{slash}4_P") (class "Default")
      (node (ref "C20") (pin "1") (pinfunction "1_1") (pintype "passive"))
      (node (ref "IC3") (pin "14") (pinfunction "CLK2_14") (pintype "output"))
      (node (ref "R21") (pin "2") (pinfunction "2_2") (pintype "passive"))
    )
    (net (code "18") (name "/FILT+") (class "Default")
      (node (ref "FL1") (pin "1") (pinfunction "B_1") (pintype "passive"))
      (node (ref "J8") (pin "3") (pinfunction "3_3") (pintype "bidirectional"))
      (node (ref "J8") (pin "4") (pinfunction "4_4") (pintype "bidirectional"))
    )
    (net (code "19") (name "/FILT-") (class "Default")
      (node (ref "FL1") (pin "3") (pinfunction "PSG_3") (pintype "passive"))
      (node (ref "J8") (pin "1") (pinfunction "1_1") (pintype "bidirectional"))
      (node (ref "J8") (pin "2") (pinfunction "2_2") (pintype "bidirectional"))
    )
    (net (code "20") (name "/LVDS_CLK_OUT_N") (class "Default")
      (node (ref "C2") (pin "1") (pinfunction "1_1") (pintype "passive"))
      (node (ref "J1") (pin "2") (pinfunction "2_2") (pintype "bidirectional"))
    )
    (net (code "21") (name "/LVDS_CLK_OUT_P") (class "Default")
      (node (ref "C1") (pin "2") (pinfunction "2_2") (pintype "passive"))
      (node (ref "J1") (pin "1") (pinfunction "1_1") (pintype "bidirectional"))
    )
    (net (code "22") (name "/LVDS_R_CLK_OUT_N") (class "Default")
      (node (ref "C2") (pin "2") (pinfunction "2_2") (pintype "passive"))
      (node (ref "R2") (pin "2") (pinfunction "2_2") (pintype "passive"))
    )
    (net (code "23") (name "/LVDS_R_CLK_OUT_P") (class "Default")
      (node (ref "C1") (pin "1") (pinfunction "1_1") (pintype "passive"))
      (node (ref "R1") (pin "2") (pinfunction "2_2") (pintype "passive"))
    )
    (net (code "24") (name "/LVPECL_CLK_OUT_0") (class "Default")
      (node (ref "C3") (pin "2") (pinfunction "2_2") (pintype "passive"))
      (node (ref "J2") (pin "1") (pinfunction "1_1") (pintype "bidirectional"))
    )
    (net (code "25") (name "/LVPECL_CLK_OUT_1") (class "Default")
      (node (ref "C21") (pin "2") (pinfunction "2_2") (pintype "passive"))
      (node (ref "J3") (pin "1") (pinfunction "1_1") (pintype "bidirectional"))
    )
    (net (code "26") (name "/NB3N3020_SEL0") (class "Default")
      (node (ref "B8") (pin "1") (pinfunction "1_1") (pintype "bidirectional"))
      (node (ref "IC3") (pin "6") (pinfunction "Sel0_6") (pintype "input"))
      (node (ref "SW1") (pin "2") (pinfunction "C_2") (pintype "bidirectional"))
    )
    (net (code "27") (name "/NB3N3020_SEL1") (class "Default")
      (node (ref "B9") (pin "1") (pinfunction "1_1") (pintype "bidirectional"))
      (node (ref "IC3") (pin "5") (pinfunction "Sel1_5") (pintype "input"))
      (node (ref "SW1") (pin "5") (pinfunction "C_5") (pintype "bidirectional"))
      (node (ref "T2") (pin "1") (pinfunction "G_1") (pintype "passive"))
    )
    (net (code "28") (name "/NB3N3020_SEL2") (class "Default")
      (node (ref "B10") (pin "1") (pinfunction "1_1") (pintype "bidirectional"))
      (node (ref "IC3") (pin "4") (pinfunction "Sel2_4") (pintype "input"))
    )
    (net (code "29") (name "/OSC_80M_N") (class "Default")
      (node (ref "C51") (pin "2") (pinfunction "2_2") (pintype "passive"))
      (node (ref "OSC1") (pin "5") (pinfunction "~{OUT}_5") (pintype "output"))
    )
    (net (code "30") (name "/OSC_80M_P") (class "Default")
      (node (ref "C52") (pin "2") (pinfunction "2_2") (pintype "passive"))
      (node (ref "OSC1") (pin "4") (pinfunction "OUT_4") (pintype "output"))
    )
    (net (code "31") (name "/OSC_VCC") (class "Default")
      (node (ref "C5") (pin "2") (pinfunction "2_2") (pintype "passive"))
      (node (ref "L3") (pin "2") (pinfunction "2_2") (pintype "passive"))
      (node (ref "OSC1") (pin "1") (pinfunction "E/D_1") (pintype "input"))
      (node (ref "OSC1") (pin "6") (pinfunction "VDD_6") (pintype "power_in"))
    )
    (net (code "32") (name "/RD_N") (class "Default")
      (node (ref "J5") (pin "12") (pinfunction "RD-_12") (pintype "output"))
      (node (ref "R7") (pin "2") (pinfunction "2_2") (pintype "passive"))
    )
    (net (code "33") (name "/RD_P") (class "Default")
      (node (ref "J5") (pin "13") (pinfunction "RD+_13") (pintype "output"))
      (node (ref "R7") (pin "1") (pinfunction "1_1") (pintype "passive"))
    )
    (net (code "34") (name "/SFP_VCCR") (class "Default")
      (node (ref "B1") (pin "1") (pinfunction "1_1") (pintype "bidirectional"))
      (node (ref "C6") (pin "1") (pinfunction "1_1") (pintype "passive"))
      (node (ref "C7") (pin "2") (pinfunction "2_2") (pintype "passive"))
      (node (ref "J5") (pin "15") (pinfunction "VCCR_15") (pintype "power_in"))
      (node (ref "L1") (pin "1") (pinfunction "1_1") (pintype "passive"))
    )
    (net (code "35") (name "/SFP_VCCT") (class "Default")
      (node (ref "B6") (pin "1") (pinfunction "1_1") (pintype "bidirectional"))
      (node (ref "C10") (pin "1") (pinfunction "1_1") (pintype "passive"))
      (node (ref "C11") (pin "2") (pinfunction "2_2") (pintype "passive"))
      (node (ref "J5") (pin "16") (pinfunction "VCCT_16") (pintype "power_in"))
      (node (ref "L2") (pin "1") (pinfunction "1_1") (pintype "passive"))
    )
    (net (code "36") (name "/SY89202_DIVSEL1") (class "Default")
      (node (ref "B2") (pin "1") (pinfunction "1_1") (pintype "bidirectional"))
      (node (ref "IC1") (pin "2") (pinfunction "DIVSEL1_2") (pintype "input"))
      (node (ref "R18") (pin "2") (pinfunction "2_2") (pintype "passive"))
      (node (ref "R25") (pin "1") (pinfunction "1_1") (pintype "passive"))
      (node (ref "SW2") (pin "5") (pinfunction "C_5") (pintype "bidirectional"))
    )
    (net (code "37") (name "/SY89202_DIVSEL2") (class "Default")
      (node (ref "B3") (pin "1") (pinfunction "1_1") (pintype "bidirectional"))
      (node (ref "IC1") (pin "7") (pinfunction "DIVSEL2_7") (pintype "input"))
      (node (ref "R19") (pin "2") (pinfunction "2_2") (pintype "passive"))
      (node (ref "R31") (pin "1") (pinfunction "1_1") (pintype "passive"))
    )
    (net (code "38") (name "/SY89202_DIVSEL3") (class "Default")
      (node (ref "B4") (pin "1") (pinfunction "1_1") (pintype "bidirectional"))
      (node (ref "IC1") (pin "8") (pinfunction "DIVSEL3_8") (pintype "input"))
      (node (ref "R20") (pin "2") (pinfunction "2_2") (pintype "passive"))
      (node (ref "R32") (pin "1") (pinfunction "1_1") (pintype "passive"))
    )
    (net (code "39") (name "/SY89202_EN") (class "Default")
      (node (ref "B5") (pin "1") (pinfunction "1_1") (pintype "bidirectional"))
      (node (ref "IC1") (pin "9") (pinfunction "EN_9") (pintype "input"))
      (node (ref "R22") (pin "2") (pinfunction "2_2") (pintype "passive"))
      (node (ref "R33") (pin "1") (pinfunction "1_1") (pintype "passive"))
    )
    (net (code "40") (name "/SY89202_IN_N") (class "Default")
      (node (ref "C52") (pin "1") (pinfunction "1_1") (pintype "passive"))
      (node (ref "IC1") (pin "6") (pinfunction "~{IN}_6") (pintype "input"))
    )
    (net (code "41") (name "/SY89202_IN_P") (class "Default")
      (node (ref "C51") (pin "1") (pinfunction "1_1") (pintype "passive"))
      (node (ref "IC1") (pin "3") (pinfunction "IN_3") (pintype "input"))
    )
    (net (code "42") (name "/SY89202_MRn") (class "Default")
      (node (ref "B7") (pin "1") (pinfunction "1_1") (pintype "bidirectional"))
      (node (ref "IC1") (pin "32") (pinfunction "~{MR}_32") (pintype "input"))
      (node (ref "R23") (pin "2") (pinfunction "2_2") (pintype "passive"))
      (node (ref "R34") (pin "1") (pinfunction "1_1") (pintype "passive"))
    )
    (net (code "43") (name "/TPSM_FB") (class "Default")
      (node (ref "C34") (pin "1") (pinfunction "1_1") (pintype "passive"))
      (node (ref "IC4") (pin "9") (pinfunction "FB_9") (pintype "input"))
      (node (ref "R26") (pin "1") (pinfunction "1_1") (pintype "passive"))
      (node (ref "R27") (pin "1") (pinfunction "1_1") (pintype "passive"))
    )
    (net (code "44") (name "/TPSM_RT") (class "Default")
      (node (ref "IC4") (pin "11") (pinfunction "RT_11") (pintype "input"))
      (node (ref "R28") (pin "2") (pinfunction "2_2") (pintype "passive"))
    )
    (net (code "45") (name "/TPSM_VCC") (class "Default")
      (node (ref "B18") (pin "1") (pinfunction "1_1") (pintype "bidirectional"))
      (node (ref "C39") (pin "2") (pinfunction "2_2") (pintype "passive"))
      (node (ref "IC4") (pin "8") (pinfunction "VCC_8") (pintype "power_in"))
    )
    (net (code "46") (name "/TPSM_VIN") (class "Default")
      (node (ref "B14") (pin "1") (pinfunction "1_1") (pintype "bidirectional"))
      (node (ref "C27") (pin "1") (pinfunction "1_1") (pintype "passive"))
      (node (ref "C28") (pin "1") (pinfunction "1_1") (pintype "passive"))
      (node (ref "C29") (pin "2") (pinfunction "2_2") (pintype "passive"))
      (node (ref "C30") (pin "2") (pinfunction "2_2") (pintype "passive"))
      (node (ref "C31") (pin "2") (pinfunction "2_2") (pintype "passive"))
      (node (ref "D1") (pin "1") (pinfunction "C_1") (pintype "passive"))
      (node (ref "D2") (pin "1") (pinfunction "C_1") (pintype "passive"))
      (node (ref "IC4") (pin "2") (pinfunction "EN_2") (pintype "input"))
      (node (ref "IC4") (pin "3") (pinfunction "VIN_3") (pintype "power_in"))
    )
    (net (code "47") (name "/TPSM_VOUT") (class "Default")
      (node (ref "B15") (pin "1") (pinfunction "1_1") (pintype "bidirectional"))
      (node (ref "C34") (pin "2") (pinfunction "2_2") (pintype "passive"))
      (node (ref "C35") (pin "2") (pinfunction "2_2") (pintype "passive"))
      (node (ref "C36") (pin "2") (pinfunction "2_2") (pintype "passive"))
      (node (ref "C37") (pin "2") (pinfunction "2_2") (pintype "passive"))
      (node (ref "IC4") (pin "4") (pinfunction "VOUT_4") (pintype "power_in"))
      (node (ref "L7") (pin "1") (pinfunction "1_1") (pintype "passive"))
      (node (ref "R26") (pin "2") (pinfunction "2_2") (pintype "passive"))
    )
    (net (code "48") (name "GND") (class "Default")
      (node (ref "B11") (pin "1") (pinfunction "1_1") (pintype "bidirectional"))
      (node (ref "B12") (pin "1") (pinfunction "1_1") (pintype "bidirectional"))
      (node (ref "B21") (pin "1") (pinfunction "1_1") (pintype "bidirectional"))
      (node (ref "B22") (pin "1") (pinfunction "1_1") (pintype "bidirectional"))
      (node (ref "B23") (pin "1") (pinfunction "1_1") (pintype "bidirectional"))
      (node (ref "B24") (pin "1") (pinfunction "1_1") (pintype "bidirectional"))
      (node (ref "C10") (pin "2") (pinfunction "2_2") (pintype "passive"))
      (node (ref "C11") (pin "1") (pinfunction "1_1") (pintype "passive"))
      (node (ref "C12") (pin "1") (pinfunction "1_1") (pintype "passive"))
      (node (ref "C13") (pin "1") (pinfunction "1_1") (pintype "passive"))
      (node (ref "C14") (pin "1") (pinfunction "1_1") (pintype "passive"))
      (node (ref "C15") (pin "1") (pinfunction "1_1") (pintype "passive"))
      (node (ref "C16") (pin "1") (pinfunction "1_1") (pintype "passive"))
      (node (ref "C17") (pin "1") (pinfunction "1_1") (pintype "passive"))
      (node (ref "C18") (pin "1") (pinfunction "1_1") (pintype "passive"))
      (node (ref "C19") (pin "1") (pinfunction "1_1") (pintype "passive"))
      (node (ref "C22") (pin "1") (pinfunction "1_1") (pintype "passive"))
      (node (ref "C23") (pin "2") (pinfunction "2_2") (pintype "passive"))
      (node (ref "C24") (pin "1") (pinfunction "1_1") (pintype "passive"))
      (node (ref "C25") (pin "1") (pinfunction "1_1") (pintype "passive"))
      (node (ref "C26") (pin "1") (pinfunction "1_1") (pintype "passive"))
      (node (ref "C27") (pin "2") (pinfunction "2_2") (pintype "passive"))
      (node (ref "C28") (pin "2") (pinfunction "2_2") (pintype "passive"))
      (node (ref "C29") (pin "1") (pinfunction "1_1") (pintype "passive"))
      (node (ref "C30") (pin "1") (pinfunction "1_1") (pintype "passive"))
      (node (ref "C31") (pin "1") (pinfunction "1_1") (pintype "passive"))
      (node (ref "C32") (pin "2") (pinfunction "2_2") (pintype "passive"))
      (node (ref "C33") (pin "2") (pinfunction "2_2") (pintype "passive"))
      (node (ref "C35") (pin "1") (pinfunction "1_1") (pintype "passive"))
      (node (ref "C36") (pin "1") (pinfunction "1_1") (pintype "passive"))
      (node (ref "C37") (pin "1") (pinfunction "1_1") (pintype "passive"))
      (node (ref "C38") (pin "1") (pinfunction "1_1") (pintype "passive"))
      (node (ref "C39") (pin "1") (pinfunction "1_1") (pintype "passive"))
      (node (ref "C4") (pin "1") (pinfunction "1_1") (pintype "passive"))
      (node (ref "C40") (pin "2") (pinfunction "2_2") (pintype "passive"))
      (node (ref "C41") (pin "2") (pinfunction "2_2") (pintype "passive"))
      (node (ref "C45") (pin "1") (pinfunction "1_1") (pintype "passive"))
      (node (ref "C46") (pin "2") (pinfunction "2_2") (pintype "passive"))
      (node (ref "C47") (pin "1") (pinfunction "1_1") (pintype "passive"))
      (node (ref "C48") (pin "1") (pinfunction "1_1") (pintype "passive"))
      (node (ref "C49") (pin "1") (pinfunction "1_1") (pintype "passive"))
      (node (ref "C5") (pin "1") (pinfunction "1_1") (pintype "passive"))
      (node (ref "C50") (pin "1") (pinfunction "1_1") (pintype "passive"))
      (node (ref "C6") (pin "2") (pinfunction "2_2") (pintype "passive"))
      (node (ref "C7") (pin "1") (pinfunction "1_1") (pintype "passive"))
      (node (ref "Cage1") (pin "1") (pinfunction "CAGE_1") (pintype "power_in"))
      (node (ref "Cage1") (pin "10") (pinfunction "CAGE_10") (pintype "power_in"))
      (node (ref "Cage1") (pin "11") (pinfunction "CAGE_11") (pintype "power_in"))
      (node (ref "Cage1") (pin "12") (pinfunction "CAGE_12") (pintype "power_in"))
      (node (ref "Cage1") (pin "13") (pinfunction "CAGE_13") (pintype "power_in"))
      (node (ref "Cage1") (pin "14") (pinfunction "CAGE_14") (pintype "power_in"))
      (node (ref "Cage1") (pin "15") (pinfunction "CAGE_15") (pintype "power_in"))
      (node (ref "Cage1") (pin "16") (pinfunction "CAGE_16") (pintype "power_in"))
      (node (ref "Cage1") (pin "17") (pinfunction "CAGE_17") (pintype "power_in"))
      (node (ref "Cage1") (pin "18") (pinfunction "CAGE_18") (pintype "power_in"))
      (node (ref "Cage1") (pin "19") (pinfunction "CAGE_19") (pintype "power_in"))
      (node (ref "Cage1") (pin "2") (pinfunction "CAGE_2") (pintype "power_in"))
      (node (ref "Cage1") (pin "20") (pinfunction "CAGE_20") (pintype "power_in"))
      (node (ref "Cage1") (pin "3") (pinfunction "CAGE_3") (pintype "power_in"))
      (node (ref "Cage1") (pin "4") (pinfunction "CAGE_4") (pintype "power_in"))
      (node (ref "Cage1") (pin "5") (pinfunction "CAGE_5") (pintype "power_in"))
      (node (ref "Cage1") (pin "6") (pinfunction "CAGE_6") (pintype "power_in"))
      (node (ref "Cage1") (pin "7") (pinfunction "CAGE_7") (pintype "power_in"))
      (node (ref "Cage1") (pin "8") (pinfunction "CAGE_8") (pintype "power_in"))
      (node (ref "Cage1") (pin "9") (pinfunction "CAGE_9") (pintype "power_in"))
      (node (ref "FL1") (pin "4") (pinfunction "CG_4") (pintype "passive"))
      (node (ref "IC1") (pin "1") (pinfunction "GND_1") (pintype "power_in"))
      (node (ref "IC1") (pin "20") (pinfunction "GND_20") (pintype "power_in"))
      (node (ref "IC1") (pin "21") (pinfunction "GND_21") (pintype "power_in"))
      (node (ref "IC1") (pin "33") (pinfunction "GND_33") (pintype "power_in"))
      (node (ref "IC3") (pin "12") (pinfunction "GND_12") (pintype "power_in"))
      (node (ref "IC3") (pin "16") (pinfunction "OE2_16") (pintype "input"))
      (node (ref "IC3") (pin "8") (pinfunction "GND_8") (pintype "power_in"))
      (node (ref "IC3") (pin "9") (pinfunction "GND_9") (pintype "power_in"))
      (node (ref "IC4") (pin "10") (pinfunction "GND_10") (pintype "power_in"))
      (node (ref "IC5") (pin "2") (pinfunction "GND_2") (pintype "power_in"))
      (node (ref "IC5") (pin "4") (pinfunction "GND_4") (pintype "power_in"))
      (node (ref "J1") (pin "3") (pinfunction "3_3") (pintype "bidirectional"))
      (node (ref "J2") (pin "2") (pinfunction "2_2") (pintype "bidirectional"))
      (node (ref "J3") (pin "2") (pinfunction "2_2") (pintype "bidirectional"))
      (node (ref "J4") (pin "2") (pinfunction "2_2") (pintype "bidirectional"))
      (node (ref "J5") (pin "1") (pinfunction "VEET_1") (pintype "power_in"))
      (node (ref "J5") (pin "10") (pinfunction "VEER_10") (pintype "power_in"))
      (node (ref "J5") (pin "11") (pinfunction "VEER_11") (pintype "power_in"))
      (node (ref "J5") (pin "14") (pinfunction "VEER_14") (pintype "power_in"))
      (node (ref "J5") (pin "17") (pinfunction "VEET_17") (pintype "power_in"))
      (node (ref "J5") (pin "20") (pinfunction "VEET_20") (pintype "power_in"))
      (node (ref "J5") (pin "9") (pinfunction "VEER_9") (pintype "power_in"))
      (node (ref "J6") (pin "2") (pinfunction "2_2") (pintype "bidirectional"))
      (node (ref "J9") (pin "A1") (pinfunction "GND_A1") (pintype "power_in"))
      (node (ref "J9") (pin "A12") (pinfunction "GND_A12") (pintype "power_in"))
      (node (ref "J9") (pin "B1") (pinfunction "GND_B1") (pintype "power_in"))
      (node (ref "J9") (pin "B12") (pinfunction "GND_B12") (pintype "power_in"))
      (node (ref "J9") (pin "SHIELD") (pinfunction "SHIELD_SHIELD") (pintype "power_in"))
      (node (ref "OSC1") (pin "3") (pinfunction "GND_3") (pintype "power_in"))
      (node (ref "R10") (pin "1") (pinfunction "1_1") (pintype "passive"))
      (node (ref "R16") (pin "1") (pinfunction "1_1") (pintype "passive"))
      (node (ref "R17") (pin "1") (pinfunction "1_1") (pintype "passive"))
      (node (ref "R21") (pin "1") (pinfunction "1_1") (pintype "passive"))
      (node (ref "R25") (pin "2") (pinfunction "2_2") (pintype "passive"))
      (node (ref "R27") (pin "2") (pinfunction "2_2") (pintype "passive"))
      (node (ref "R28") (pin "1") (pinfunction "1_1") (pintype "passive"))
      (node (ref "R29") (pin "2") (pinfunction "2_2") (pintype "passive"))
      (node (ref "R3") (pin "1") (pinfunction "1_1") (pintype "passive"))
      (node (ref "R30") (pin "2") (pinfunction "2_2") (pintype "passive"))
      (node (ref "R31") (pin "2") (pinfunction "2_2") (pintype "passive"))
      (node (ref "R32") (pin "2") (pinfunction "2_2") (pintype "passive"))
      (node (ref "R33") (pin "2") (pinfunction "2_2") (pintype "passive"))
      (node (ref "R34") (pin "2") (pinfunction "2_2") (pintype "passive"))
      (node (ref "R36") (pin "1") (pinfunction "1_1") (pintype "passive"))
      (node (ref "R4") (pin "1") (pinfunction "1_1") (pintype "passive"))
      (node (ref "R40") (pin "1") (pinfunction "1_1") (pintype "passive"))
      (node (ref "R43") (pin "1") (pinfunction "1_1") (pintype "passive"))
      (node (ref "R44") (pin "1") (pinfunction "1_1") (pintype "passive"))
      (node (ref "R45") (pin "1") (pinfunction "1_1") (pintype "passive"))
      (node (ref "R46") (pin "1") (pinfunction "1_1") (pintype "passive"))
      (node (ref "R47") (pin "1") (pinfunction "1_1") (pintype "passive"))
      (node (ref "R5") (pin "1") (pinfunction "1_1") (pintype "passive"))
      (node (ref "R6") (pin "1") (pinfunction "1_1") (pintype "passive"))
      (node (ref "R9") (pin "1") (pinfunction "1_1") (pintype "passive"))
      (node (ref "SW1") (pin "6") (pinfunction "NO_6") (pintype "bidirectional"))
      (node (ref "SW2") (pin "3") (pinfunction "NO_3") (pintype "bidirectional"))
      (node (ref "SW2") (pin "6") (pinfunction "NO_6") (pintype "bidirectional"))
      (node (ref "T1") (pin "2") (pinfunction "S_2") (pintype "passive"))
      (node (ref "T2") (pin "2") (pinfunction "S_2") (pintype "passive"))
      (node (ref "T3") (pin "2") (pinfunction "S_2") (pintype "passive"))
      (node (ref "T4") (pin "2") (pinfunction "S_2") (pintype "passive"))
      (node (ref "TR1") (pin "3") (pinfunction "S_3") (pintype "passive"))
    )
    (net (code "49") (name "NB3N3020_VDD") (class "Default")
      (node (ref "C23") (pin "1") (pinfunction "1_1") (pintype "passive"))
      (node (ref "C24") (pin "2") (pinfunction "2_2") (pintype "passive"))
      (node (ref "C25") (pin "2") (pinfunction "2_2") (pintype "passive"))
      (node (ref "C26") (pin "2") (pinfunction "2_2") (pintype "passive"))
      (node (ref "IC3") (pin "1") (pinfunction "VDD_1") (pintype "power_in"))
      (node (ref "IC3") (pin "11") (pinfunction "VDD_11") (pintype "power_in"))
      (node (ref "IC3") (pin "15") (pinfunction "VDD_15") (pintype "power_in"))
      (node (ref "L5") (pin "2") (pinfunction "2_2") (pintype "passive"))
      (node (ref "R41") (pin "2") (pinfunction "2_2") (pintype "passive"))
    )
    (net (code "50") (name "Net-(B19-Pad1)") (class "Default")
      (node (ref "B19") (pin "1") (pinfunction "1_1") (pintype "bidirectional"))
      (node (ref "C40") (pin "1") (pinfunction "1_1") (pintype "passive"))
      (node (ref "R29") (pin "1") (pinfunction "1_1") (pintype "passive"))
    )
    (net (code "51") (name "Net-(B20-Pad1)") (class "Default")
      (node (ref "B20") (pin "1") (pinfunction "1_1") (pintype "bidirectional"))
      (node (ref "C41") (pin "1") (pinfunction "1_1") (pintype "passive"))
      (node (ref "R30") (pin "1") (pinfunction "1_1") (pintype "passive"))
    )
    (net (code "52") (name "Net-(C8-Pad1)") (class "Default")
      (node (ref "C8") (pin "1") (pinfunction "1_1") (pintype "passive"))
      (node (ref "R37") (pin "2") (pinfunction "2_2") (pintype "passive"))
    )
    (net (code "53") (name "Net-(C9-Pad2)") (class "Default")
      (node (ref "C9") (pin "2") (pinfunction "2_2") (pintype "passive"))
      (node (ref "R38") (pin "2") (pinfunction "2_2") (pintype "passive"))
    )
    (net (code "54") (name "Net-(C46-Pad1)") (class "Default")
      (node (ref "C46") (pin "1") (pinfunction "1_1") (pintype "passive"))
      (node (ref "C47") (pin "2") (pinfunction "2_2") (pintype "passive"))
      (node (ref "L6") (pin "1") (pinfunction "1_1") (pintype "passive"))
      (node (ref "L7") (pin "2") (pinfunction "2_2") (pintype "passive"))
    )
    (net (code "55") (name "Net-(C50-Pad2)") (class "Default")
      (node (ref "C50") (pin "2") (pinfunction "2_2") (pintype "passive"))
      (node (ref "R39") (pin "2") (pinfunction "2_2") (pintype "passive"))
      (node (ref "R41") (pin "1") (pinfunction "1_1") (pintype "passive"))
      (node (ref "R43") (pin "2") (pinfunction "2_2") (pintype "passive"))
    )
    (net (code "56") (name "Net-(IC1-VREF-AC)") (class "Default")
      (node (ref "C53") (pin "1") (pinfunction "1_1") (pintype "passive"))
      (node (ref "IC1") (pin "4") (pinfunction "VT_4") (pintype "power_in"))
      (node (ref "IC1") (pin "5") (pinfunction "VREF-AC_5") (pintype "power_in"))
    )
    (net (code "57") (name "Net-(IC3-X1{slash}CLK)") (class "Default")
      (node (ref "C42") (pin "2") (pinfunction "2_2") (pintype "passive"))
      (node (ref "IC3") (pin "2") (pinfunction "X1/CLK_2") (pintype "input"))
      (node (ref "R39") (pin "1") (pinfunction "1_1") (pintype "passive"))
    )
    (net (code "58") (name "Net-(J5-LOS)") (class "Default")
      (node (ref "J5") (pin "8") (pinfunction "LOS_8") (pintype "output"))
      (node (ref "R15") (pin "1") (pinfunction "1_1") (pintype "passive"))
    )
    (net (code "59") (name "Net-(J5-MOD_DEF0)") (class "Default")
      (node (ref "J5") (pin "6") (pinfunction "MOD_DEF0_6") (pintype "output"))
      (node (ref "R13") (pin "1") (pinfunction "1_1") (pintype "passive"))
    )
    (net (code "60") (name "Net-(J5-MOD_DEF1)") (class "Default")
      (node (ref "J5") (pin "5") (pinfunction "MOD_DEF1_5") (pintype "input"))
      (node (ref "R12") (pin "1") (pinfunction "1_1") (pintype "passive"))
    )
    (net (code "61") (name "Net-(J5-MOD_DEF2)") (class "Default")
      (node (ref "J5") (pin "4") (pinfunction "MOD_DEF2_4") (pintype "bidirectional"))
      (node (ref "R11") (pin "1") (pinfunction "1_1") (pintype "passive"))
    )
    (net (code "62") (name "Net-(J5-RATE_SELECT)") (class "Default")
      (node (ref "J5") (pin "7") (pinfunction "RATE_SELECT_7") (pintype "input"))
      (node (ref "R14") (pin "1") (pinfunction "1_1") (pintype "passive"))
    )
    (net (code "63") (name "Net-(J5-TX_DISABLE)") (class "Default")
      (node (ref "J5") (pin "3") (pinfunction "TX_DISABLE_3") (pintype "input"))
      (node (ref "R16") (pin "2") (pinfunction "2_2") (pintype "passive"))
    )
    (net (code "64") (name "Net-(J5-TX_FAULT)") (class "Default")
      (node (ref "J5") (pin "2") (pinfunction "TX_FAULT_2") (pintype "output"))
      (node (ref "R8") (pin "1") (pinfunction "1_1") (pintype "passive"))
    )
    (net (code "65") (name "Net-(J9-CC1)") (class "Default")
      (node (ref "J9") (pin "A5") (pinfunction "CC1_A5") (pintype "bidirectional"))
      (node (ref "R40") (pin "2") (pinfunction "2_2") (pintype "passive"))
    )
    (net (code "66") (name "Net-(J9-CC2)") (class "Default")
      (node (ref "J9") (pin "B5") (pinfunction "CC2_B5") (pintype "bidirectional"))
      (node (ref "R47") (pin "2") (pinfunction "2_2") (pintype "passive"))
    )
    (net (code "67") (name "Net-(LD1-A)") (class "Default")
      (node (ref "LD1") (pin "2") (pinfunction "A_2") (pintype "passive"))
      (node (ref "R48") (pin "1") (pinfunction "1_1") (pintype "passive"))
    )
    (net (code "68") (name "Net-(LD1-C)") (class "Default")
      (node (ref "LD1") (pin "1") (pinfunction "C_1") (pintype "passive"))
      (node (ref "R24") (pin "1") (pinfunction "1_1") (pintype "passive"))
      (node (ref "T1") (pin "3") (pinfunction "D_3") (pintype "passive"))
      (node (ref "T4") (pin "1") (pinfunction "G_1") (pintype "passive"))
    )
    (net (code "69") (name "Net-(LD2-A)") (class "Default")
      (node (ref "LD2") (pin "2") (pinfunction "A_2") (pintype "passive"))
      (node (ref "R50") (pin "1") (pinfunction "1_1") (pintype "passive"))
    )
    (net (code "70") (name "Net-(LD2-C)") (class "Default")
      (node (ref "LD2") (pin "1") (pinfunction "C_1") (pintype "passive"))
      (node (ref "R51") (pin "1") (pinfunction "1_1") (pintype "passive"))
      (node (ref "T2") (pin "3") (pinfunction "D_3") (pintype "passive"))
      (node (ref "T3") (pin "1") (pinfunction "G_1") (pintype "passive"))
    )
    (net (code "71") (name "Net-(LD3-C)") (class "Default")
      (node (ref "LD3") (pin "1") (pinfunction "C_1") (pintype "passive"))
      (node (ref "R52") (pin "2") (pinfunction "2_2") (pintype "passive"))
    )
    (net (code "72") (name "Net-(LD4-C)") (class "Default")
      (node (ref "LD4") (pin "1") (pinfunction "C_1") (pintype "passive"))
      (node (ref "R35") (pin "2") (pinfunction "2_2") (pintype "passive"))
    )
    (net (code "73") (name "Net-(SW2A-C)") (class "Default")
      (node (ref "R49") (pin "1") (pinfunction "1_1") (pintype "passive"))
      (node (ref "SW2") (pin "2") (pinfunction "C_2") (pintype "bidirectional"))
      (node (ref "T1") (pin "1") (pinfunction "G_1") (pintype "passive"))
    )
    (net (code "74") (name "Net-(T3-D)") (class "Default")
      (node (ref "R52") (pin "1") (pinfunction "1_1") (pintype "passive"))
      (node (ref "T3") (pin "3") (pinfunction "D_3") (pintype "passive"))
    )
    (net (code "75") (name "Net-(T4-D)") (class "Default")
      (node (ref "R35") (pin "1") (pinfunction "1_1") (pintype "passive"))
      (node (ref "T4") (pin "3") (pinfunction "D_3") (pintype "passive"))
    )
    (net (code "76") (name "Net-(TR1-P)") (class "Default")
      (node (ref "C44") (pin "2") (pinfunction "2_2") (pintype "passive"))
      (node (ref "TR1") (pin "4") (pinfunction "P_4") (pintype "passive"))
    )
    (net (code "77") (name "Net-(TR1-PDOT)") (class "Default")
      (node (ref "C43") (pin "2") (pinfunction "2_2") (pintype "passive"))
      (node (ref "TR1") (pin "6") (pinfunction "PDOT_6") (pintype "passive"))
    )
    (net (code "78") (name "Net-(TR1-SDOT)") (class "Default")
      (node (ref "C42") (pin "1") (pinfunction "1_1") (pintype "passive"))
      (node (ref "TR1") (pin "1") (pinfunction "SDOT_1") (pintype "passive"))
    )
    (net (code "79") (name "P3V3") (class "Default")
      (node (ref "B16") (pin "1") (pinfunction "1_1") (pintype "bidirectional"))
      (node (ref "C22") (pin "2") (pinfunction "2_2") (pintype "passive"))
      (node (ref "C33") (pin "1") (pinfunction "1_1") (pintype "passive"))
      (node (ref "C4") (pin "2") (pinfunction "2_2") (pintype "passive"))
      (node (ref "C45") (pin "2") (pinfunction "2_2") (pintype "passive"))
      (node (ref "IC5") (pin "3") (pinfunction "OUT_3") (pintype "power_in"))
      (node (ref "L1") (pin "2") (pinfunction "2_2") (pintype "passive"))
      (node (ref "L2") (pin "2") (pinfunction "2_2") (pintype "passive"))
      (node (ref "L3") (pin "1") (pinfunction "1_1") (pintype "passive"))
      (node (ref "L4") (pin "1") (pinfunction "1_1") (pintype "passive"))
      (node (ref "L5") (pin "1") (pinfunction "1_1") (pintype "passive"))
      (node (ref "LD3") (pin "2") (pinfunction "A_2") (pintype "passive"))
      (node (ref "LD4") (pin "2") (pinfunction "A_2") (pintype "passive"))
      (node (ref "R11") (pin "2") (pinfunction "2_2") (pintype "passive"))
      (node (ref "R12") (pin "2") (pinfunction "2_2") (pintype "passive"))
      (node (ref "R13") (pin "2") (pinfunction "2_2") (pintype "passive"))
      (node (ref "R14") (pin "2") (pinfunction "2_2") (pintype "passive"))
      (node (ref "R15") (pin "2") (pinfunction "2_2") (pintype "passive"))
      (node (ref "R18") (pin "1") (pinfunction "1_1") (pintype "passive"))
      (node (ref "R19") (pin "1") (pinfunction "1_1") (pintype "passive"))
      (node (ref "R20") (pin "1") (pinfunction "1_1") (pintype "passive"))
      (node (ref "R22") (pin "1") (pinfunction "1_1") (pintype "passive"))
      (node (ref "R23") (pin "1") (pinfunction "1_1") (pintype "passive"))
      (node (ref "R24") (pin "2") (pinfunction "2_2") (pintype "passive"))
      (node (ref "R48") (pin "2") (pinfunction "2_2") (pintype "passive"))
      (node (ref "R49") (pin "2") (pinfunction "2_2") (pintype "passive"))
      (node (ref "R50") (pin "2") (pinfunction "2_2") (pintype "passive"))
      (node (ref "R51") (pin "2") (pinfunction "2_2") (pintype "passive"))
      (node (ref "R8") (pin "2") (pinfunction "2_2") (pintype "passive"))
      (node (ref "SW1") (pin "3") (pinfunction "NO_3") (pintype "bidirectional"))
      (node (ref "SW1") (pin "4") (pinfunction "NC_4") (pintype "bidirectional"))
    )
    (net (code "80") (name "P3V7") (class "Default")
      (node (ref "C32") (pin "1") (pinfunction "1_1") (pintype "passive"))
      (node (ref "C38") (pin "2") (pinfunction "2_2") (pintype "passive"))
      (node (ref "C48") (pin "2") (pinfunction "2_2") (pintype "passive"))
      (node (ref "IC5") (pin "1") (pinfunction "IN_1") (pintype "input"))
      (node (ref "L6") (pin "2") (pinfunction "2_2") (pintype "passive"))
    )
    (net (code "81") (name "P5V0_IN") (class "Default")
      (node (ref "B17") (pin "1") (pinfunction "1_1") (pintype "bidirectional"))
      (node (ref "D2") (pin "2") (pinfunction "A_2") (pintype "passive"))
      (node (ref "J9") (pin "A4") (pinfunction "VBUS_A4") (pintype "power_in"))
      (node (ref "J9") (pin "A9") (pinfunction "VBUS_A9") (pintype "power_in"))
      (node (ref "J9") (pin "B4") (pinfunction "VBUS_B4") (pintype "power_in"))
      (node (ref "J9") (pin "B9") (pinfunction "VBUS_B9") (pintype "power_in"))
    )
    (net (code "82") (name "P12V0_IN") (class "Default")
      (node (ref "B13") (pin "1") (pinfunction "1_1") (pintype "bidirectional"))
      (node (ref "C49") (pin "2") (pinfunction "2_2") (pintype "passive"))
      (node (ref "D1") (pin "2") (pinfunction "A_2") (pintype "passive"))
      (node (ref "FL1") (pin "2") (pinfunction "CB_2") (pintype "passive"))
    )
    (net (code "83") (name "SY89202_VCC") (class "Default")
      (node (ref "C12") (pin "2") (pinfunction "2_2") (pintype "passive"))
      (node (ref "C13") (pin "2") (pinfunction "2_2") (pintype "passive"))
      (node (ref "C14") (pin "2") (pinfunction "2_2") (pintype "passive"))
      (node (ref "C15") (pin "2") (pinfunction "2_2") (pintype "passive"))
      (node (ref "C16") (pin "2") (pinfunction "2_2") (pintype "passive"))
      (node (ref "C17") (pin "2") (pinfunction "2_2") (pintype "passive"))
      (node (ref "C18") (pin "2") (pinfunction "2_2") (pintype "passive"))
      (node (ref "C19") (pin "2") (pinfunction "2_2") (pintype "passive"))
      (node (ref "C53") (pin "2") (pinfunction "2_2") (pintype "passive"))
      (node (ref "IC1") (pin "10") (pinfunction "VCC_10") (pintype "power_in"))
      (node (ref "IC1") (pin "19") (pinfunction "VCC_19") (pintype "power_in"))
      (node (ref "IC1") (pin "22") (pinfunction "VCC_22") (pintype "power_in"))
      (node (ref "IC1") (pin "31") (pinfunction "VCC_31") (pintype "power_in"))
      (node (ref "L4") (pin "2") (pinfunction "2_2") (pintype "passive"))
    )
    (net (code "84") (name "unconnected-(IC1-Q2-Pad26)") (class "Default")
      (node (ref "IC1") (pin "26") (pinfunction "Q2_26") (pintype "output"))
    )
    (net (code "85") (name "unconnected-(IC1-Q3-Pad24)") (class "Default")
      (node (ref "IC1") (pin "24") (pinfunction "Q3_24") (pintype "output"))
    )
    (net (code "86") (name "unconnected-(IC1-Q4-Pad16)") (class "Default")
      (node (ref "IC1") (pin "16") (pinfunction "Q4_16") (pintype "output"))
    )
    (net (code "87") (name "unconnected-(IC1-~{Q2}-Pad25)") (class "Default")
      (node (ref "IC1") (pin "25") (pinfunction "~{Q2}_25") (pintype "output"))
    )
    (net (code "88") (name "unconnected-(IC1-~{Q3}-Pad23)") (class "Default")
      (node (ref "IC1") (pin "23") (pinfunction "~{Q3}_23") (pintype "output"))
    )
    (net (code "89") (name "unconnected-(IC1-~{Q4}-Pad15)") (class "Default")
      (node (ref "IC1") (pin "15") (pinfunction "~{Q4}_15") (pintype "output"))
    )
    (net (code "90") (name "unconnected-(IC3-OE1-Pad7)") (class "Default")
      (node (ref "IC3") (pin "7") (pinfunction "OE1_7") (pintype "input+no_connect"))
    )
    (net (code "91") (name "unconnected-(IC3-X2-Pad3)") (class "Default")
      (node (ref "IC3") (pin "3") (pinfunction "X2_3") (pintype "input+no_connect"))
    )
    (net (code "92") (name "unconnected-(IC4-BOOT-Pad7)") (class "Default")
      (node (ref "IC4") (pin "7") (pinfunction "BOOT_7") (pintype "power_in"))
    )
    (net (code "93") (name "unconnected-(IC4-PGOOD-Pad1)") (class "Default")
      (node (ref "IC4") (pin "1") (pinfunction "PGOOD_1") (pintype "output"))
    )
    (net (code "94") (name "unconnected-(IC4-SW-Pad5)") (class "Default")
      (node (ref "IC4") (pin "5") (pinfunction "SW_5") (pintype "power_in"))
    )
    (net (code "95") (name "unconnected-(IC4-SW-Pad6)") (class "Default")
      (node (ref "IC4") (pin "6") (pinfunction "SW_6") (pintype "power_in"))
    )
    (net (code "96") (name "unconnected-(J9-D1+-PadA6)") (class "Default")
      (node (ref "J9") (pin "A6") (pinfunction "D1+_A6") (pintype "bidirectional"))
    )
    (net (code "97") (name "unconnected-(J9-D1--PadA7)") (class "Default")
      (node (ref "J9") (pin "A7") (pinfunction "D1-_A7") (pintype "bidirectional"))
    )
    (net (code "98") (name "unconnected-(J9-D2+-PadB6)") (class "Default")
      (node (ref "J9") (pin "B6") (pinfunction "D2+_B6") (pintype "bidirectional"))
    )
    (net (code "99") (name "unconnected-(J9-D2--PadB7)") (class "Default")
      (node (ref "J9") (pin "B7") (pinfunction "D2-_B7") (pintype "bidirectional"))
    )
    (net (code "100") (name "unconnected-(OSC1-NC-Pad2)") (class "Default")
      (node (ref "OSC1") (pin "2") (pinfunction "NC_2") (pintype "passive"))
    )
    (net (code "101") (name "unconnected-(SW1A-NC-Pad1)") (class "Default")
      (node (ref "SW1") (pin "1") (pinfunction "NC_1") (pintype "bidirectional"))
    )
    (net (code "102") (name "unconnected-(SW2A-NC-Pad1)") (class "Default")
      (node (ref "SW2") (pin "1") (pinfunction "NC_1") (pintype "bidirectional"))
    )
    (net (code "103") (name "unconnected-(SW2B-NC-Pad4)") (class "Default")
      (node (ref "SW2") (pin "4") (pinfunction "NC_4") (pintype "bidirectional"))
    )
    (net (code "104") (name "unconnected-(TR1-NU-Pad2)") (class "Default")
      (node (ref "TR1") (pin "2") (pinfunction "NU_2") (pintype "passive"))
    )
  )
)
